# MorphingVCA.net
KiCad netlist of a schematic drawn in EAGLE
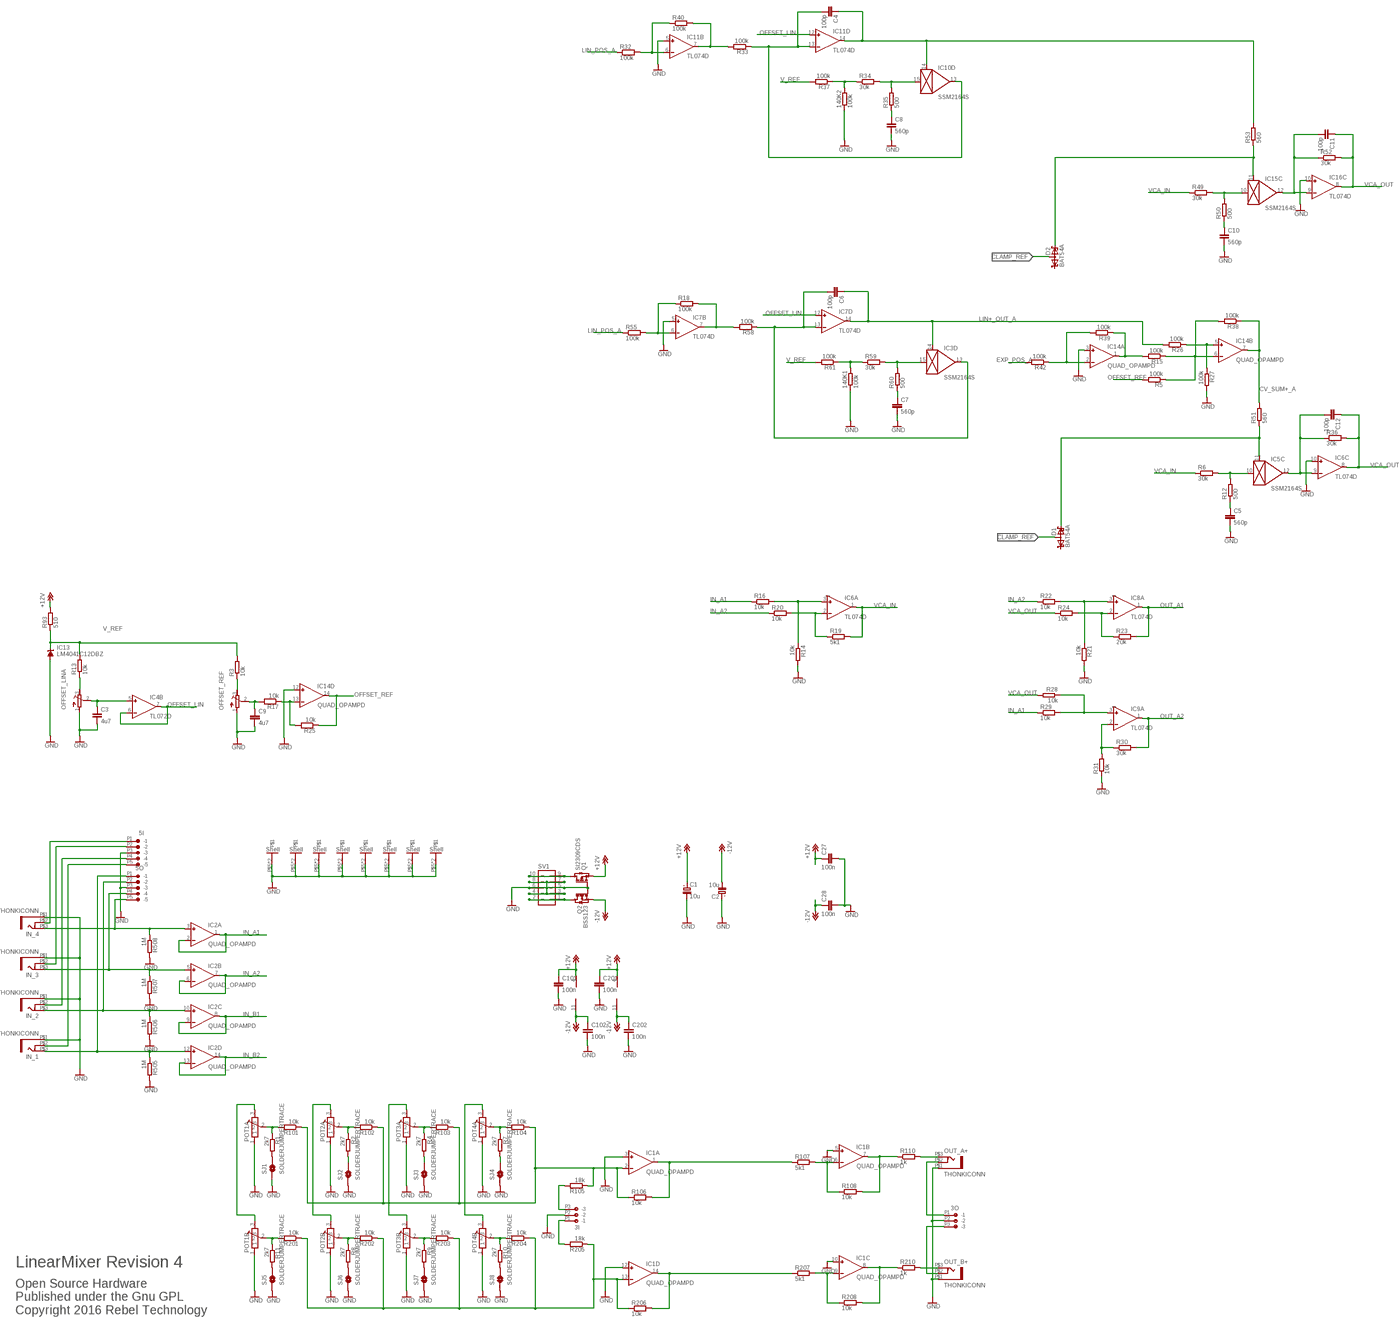
[diagram p0: schematic, sheet 1, overview]
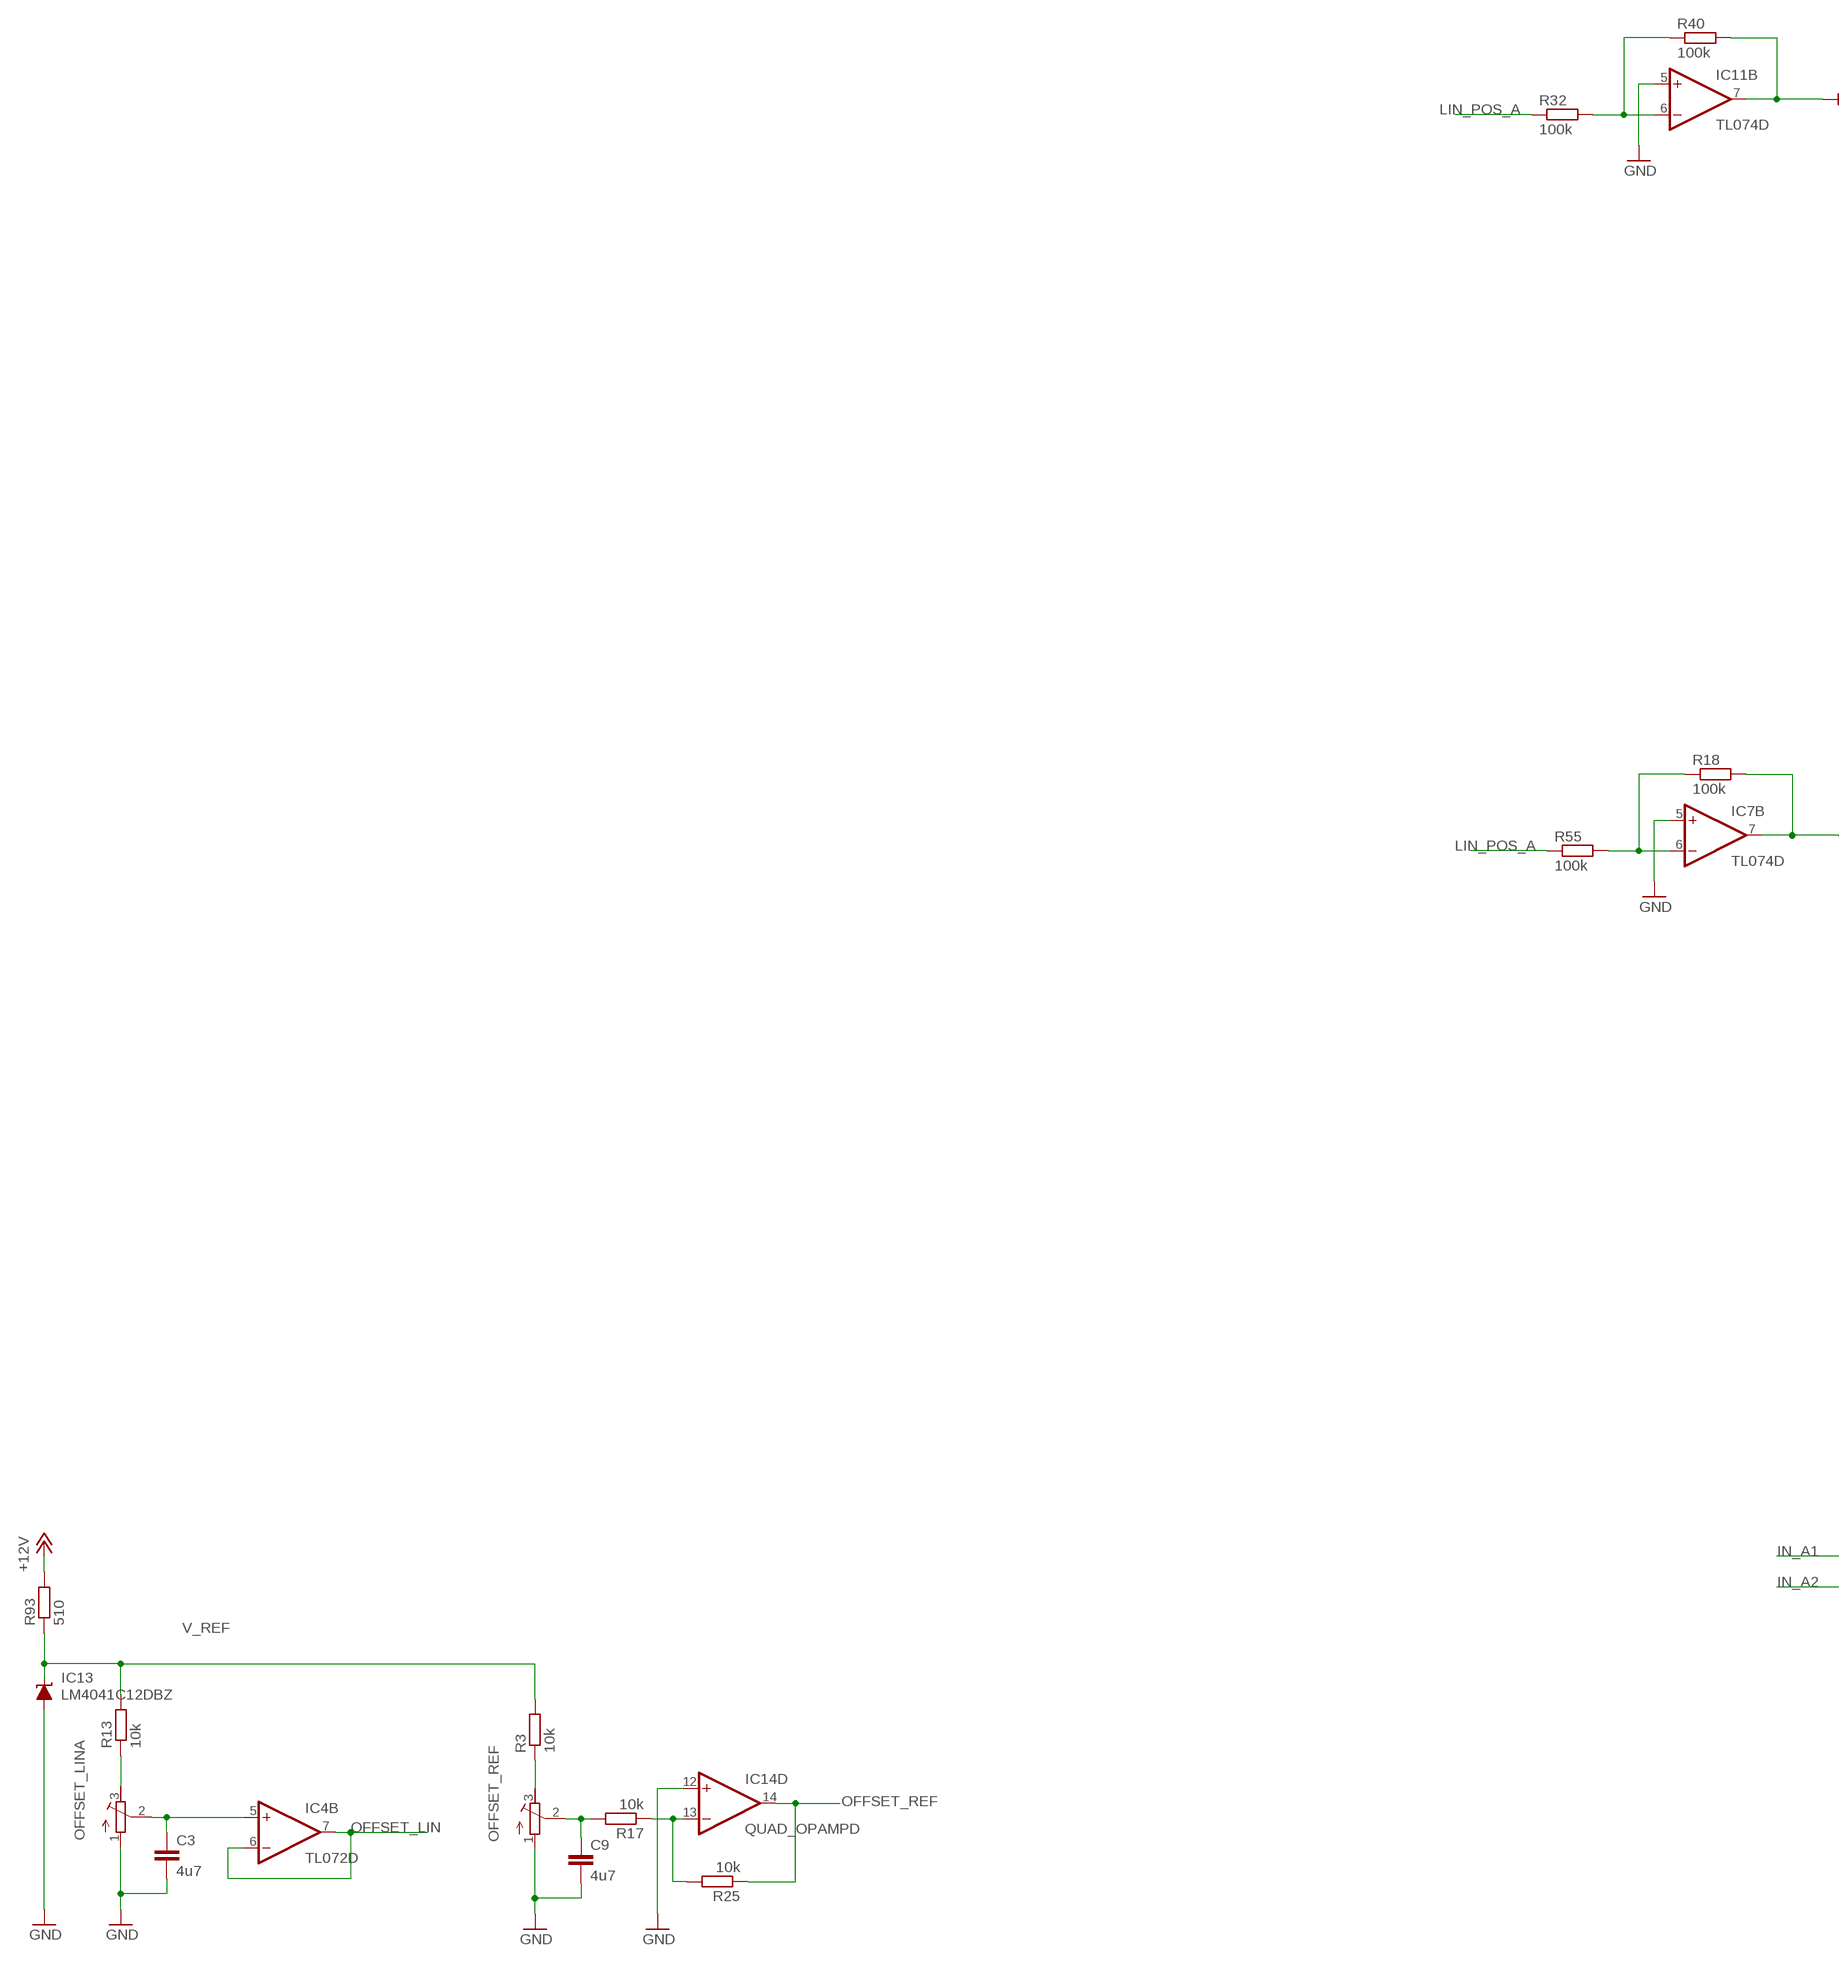
[diagram p1: schematic, sheet 1, part 1 of 4]
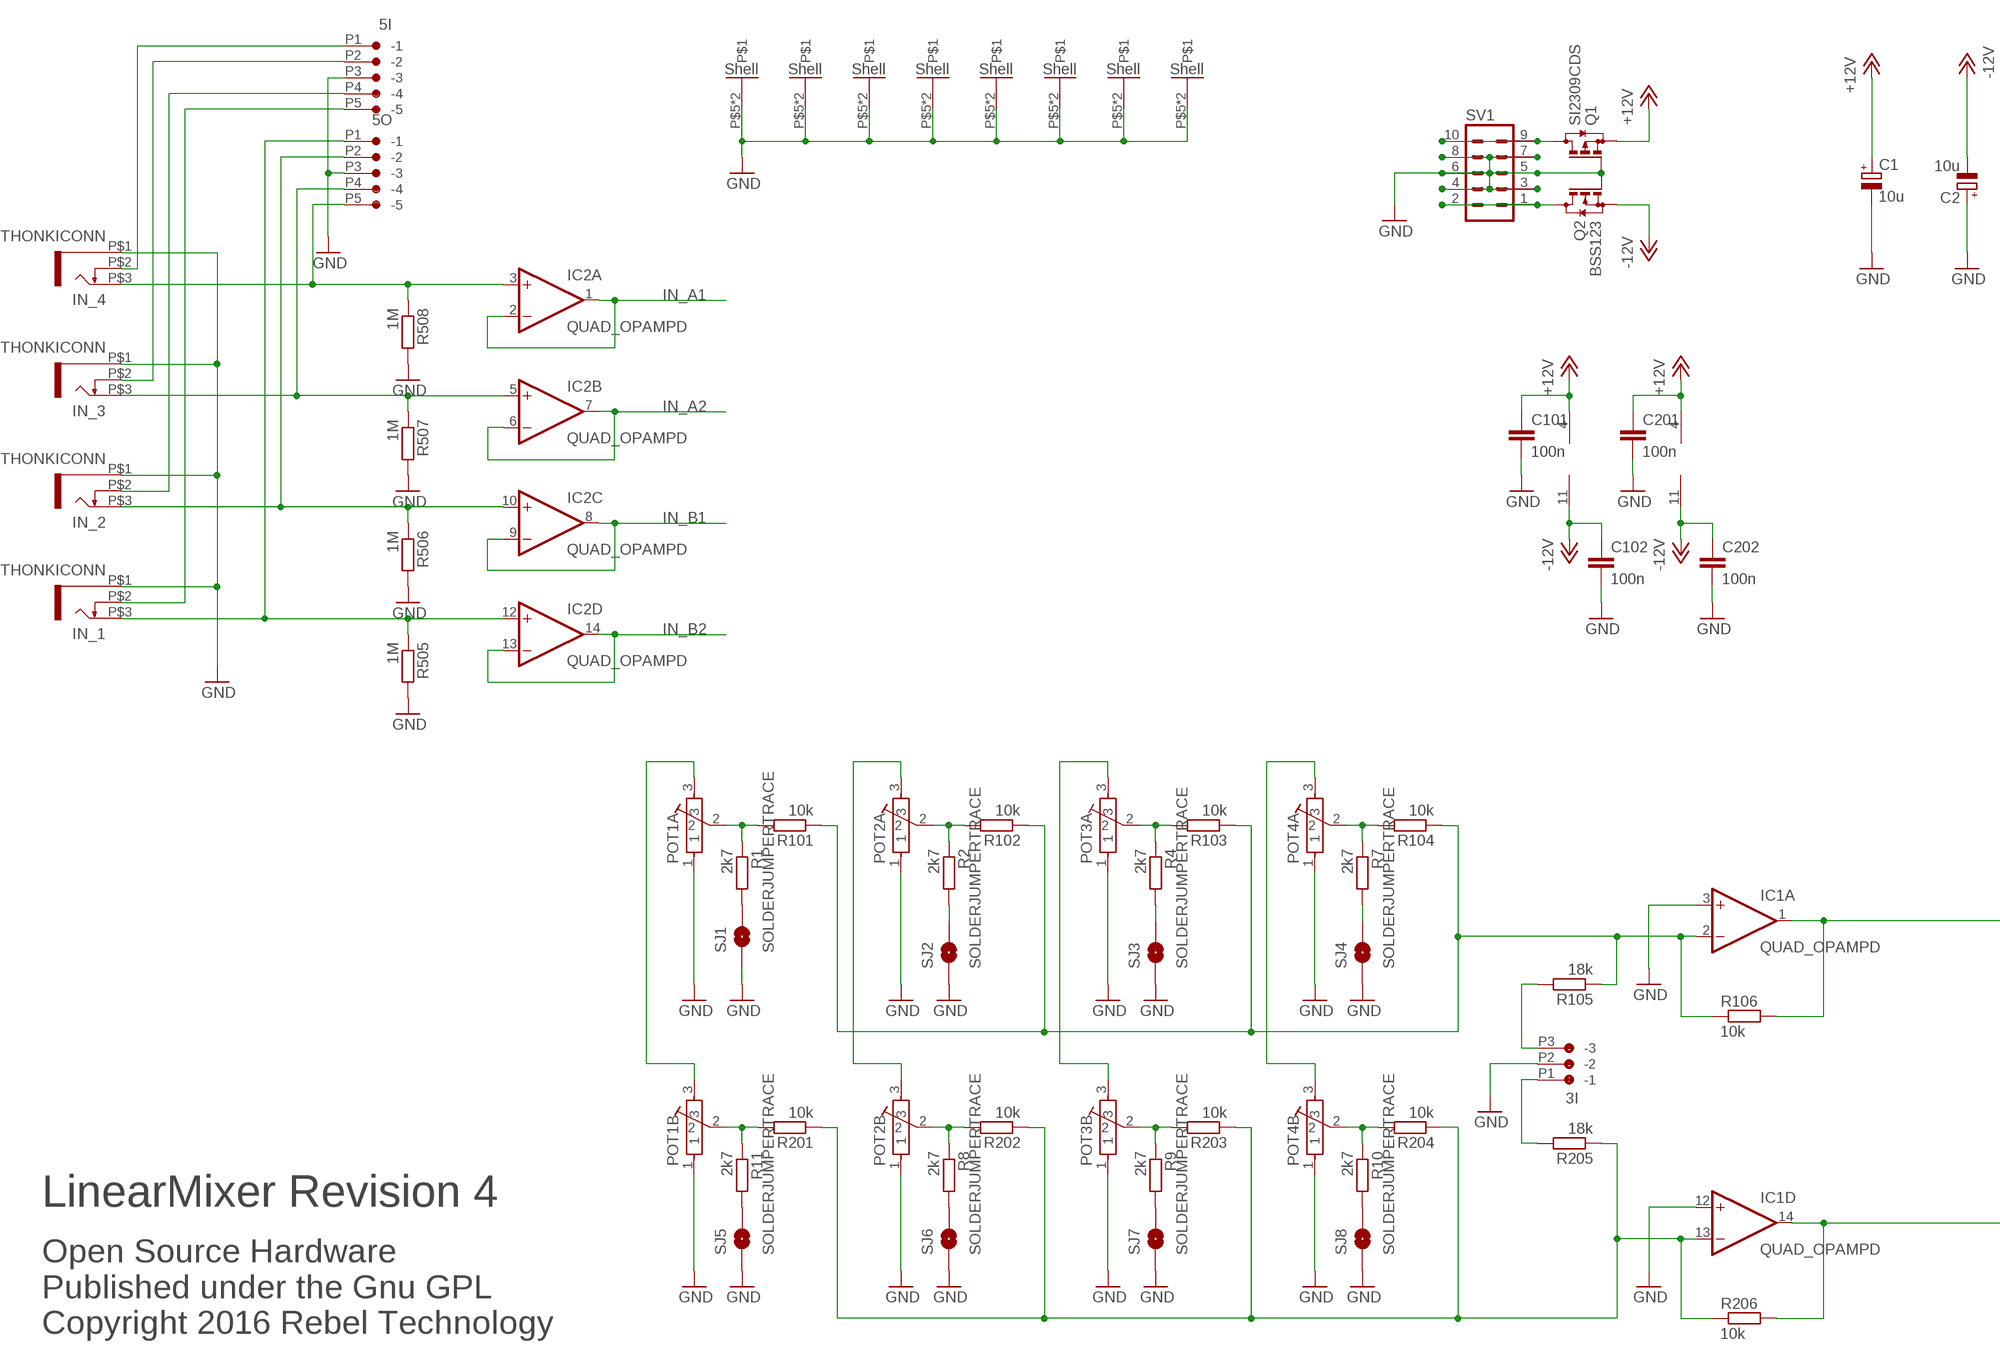
[diagram p2: schematic, sheet 1, part 2 of 4]
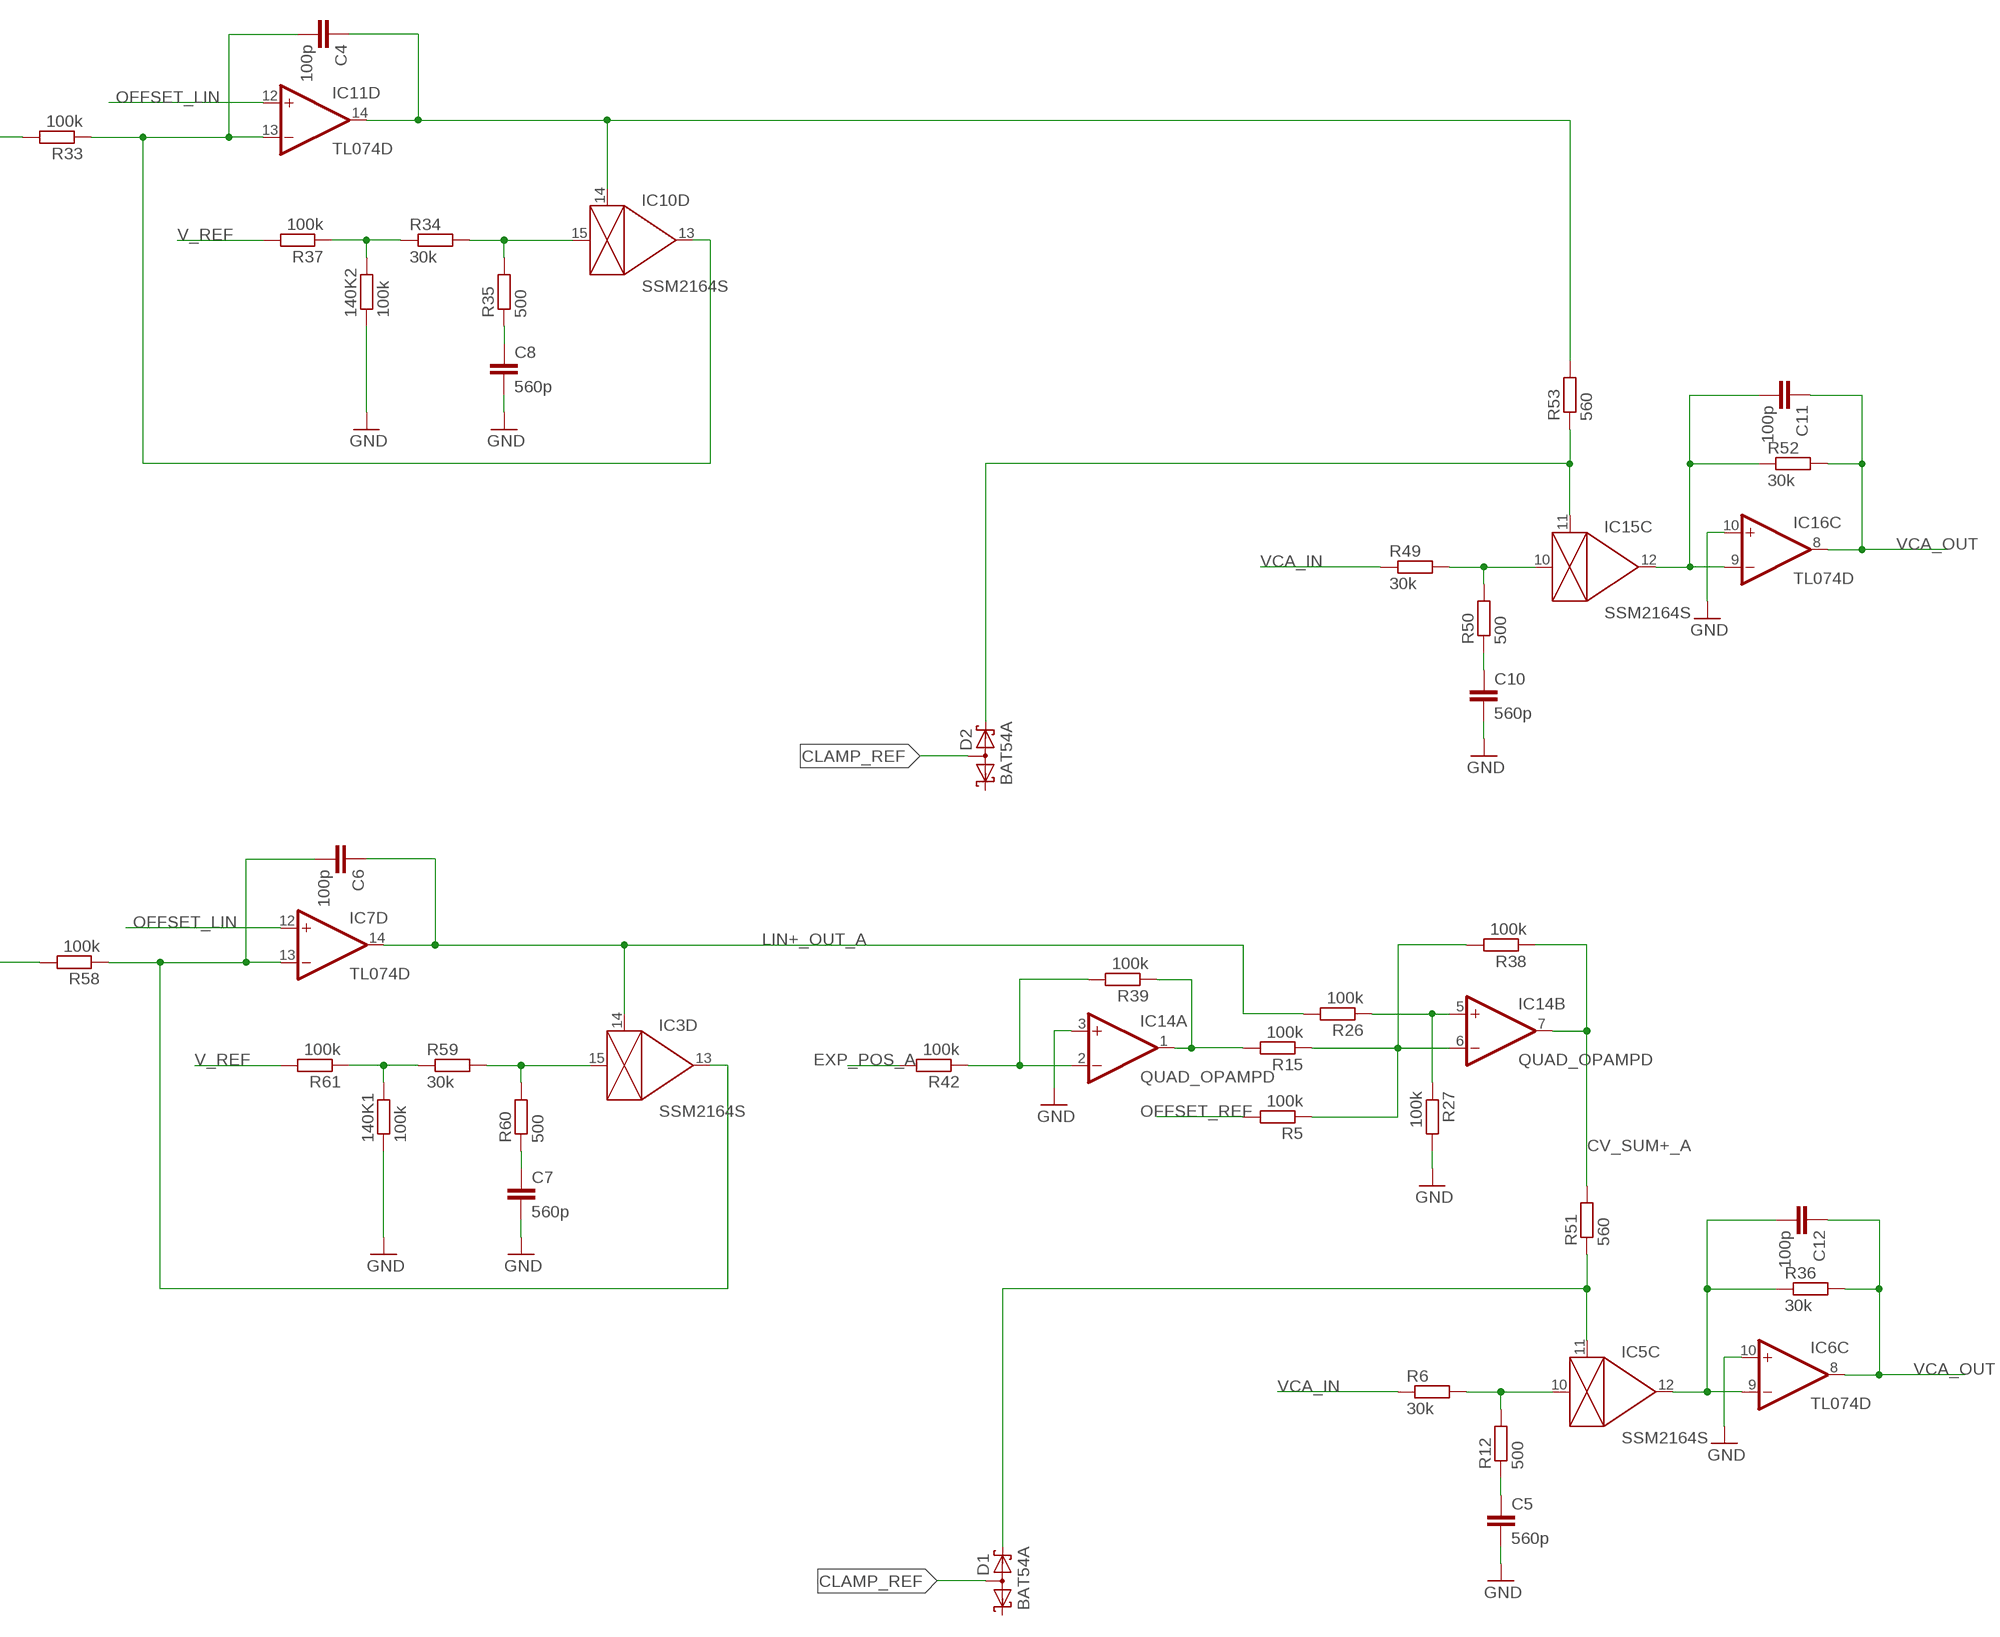
[diagram p3: schematic, sheet 1, part 3 of 4]
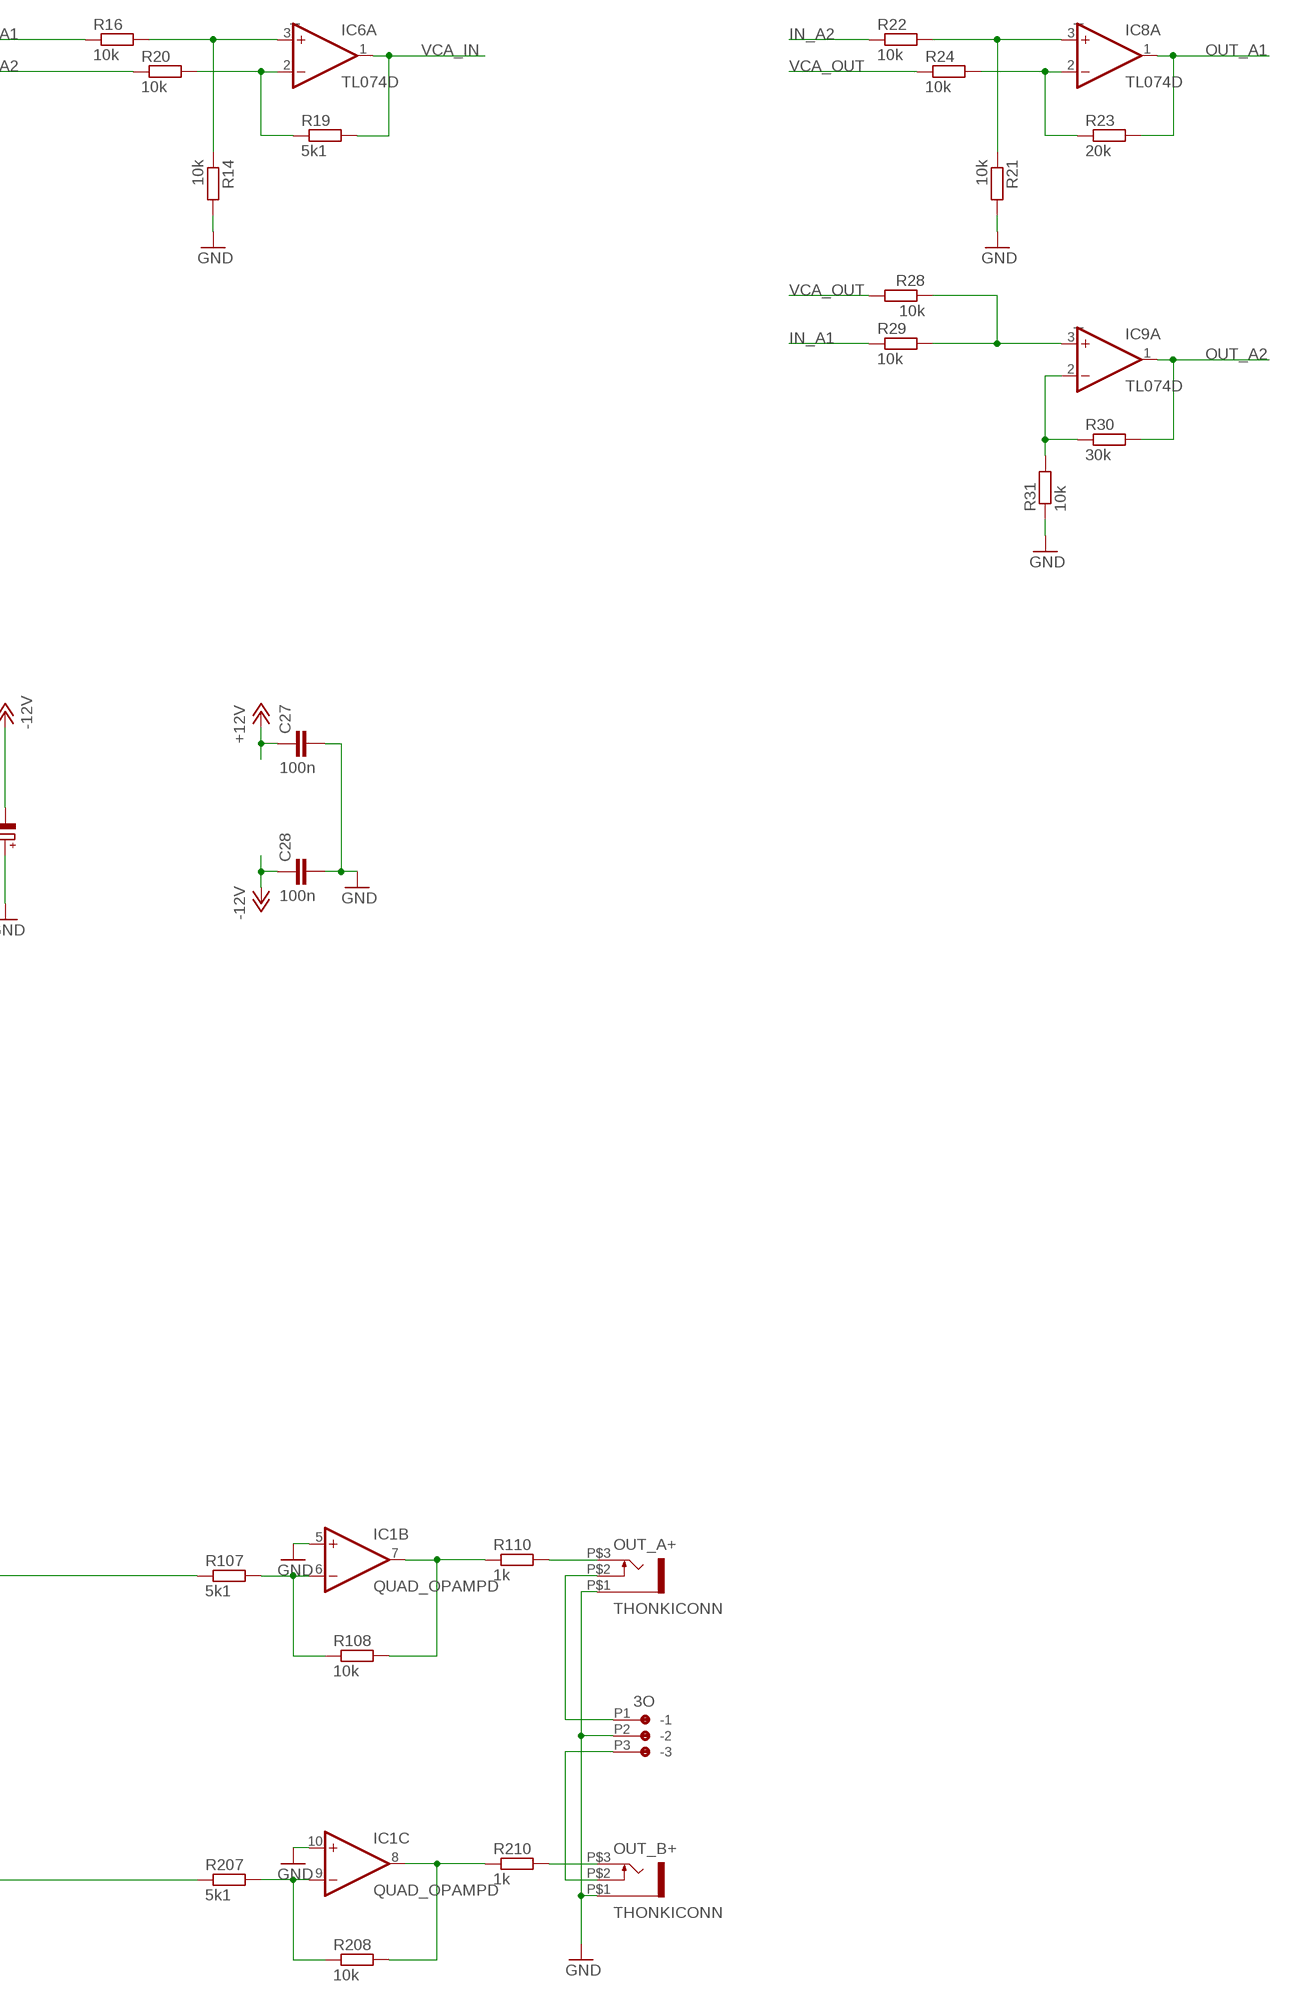
[diagram p4: schematic, sheet 1, part 4 of 4]

(export (version "E")
  (design (tool "Eeschema 10.0.6"))
  (components
    (comp (ref "3I")
      (value "CON-JST_PH_3W")
      (footprint "eagle-import:CON-JST_PH_3W")
      (libsource (lib "eagle-import") (part "CON-JST_PH_3W"))
    )
    (comp (ref "3O")
      (value "CON-JST_PH_3W")
      (footprint "eagle-import:CON-JST_PH_3W")
      (libsource (lib "eagle-import") (part "CON-JST_PH_3W"))
    )
    (comp (ref "5I")
      (value "CON-JST_PH_5W")
      (footprint "eagle-import:CON-JST_PH_5W")
      (libsource (lib "eagle-import") (part "CON-JST_PH_5W"))
    )
    (comp (ref "5O")
      (value "CON-JST_PH_5W")
      (footprint "eagle-import:CON-JST_PH_5W")
      (libsource (lib "eagle-import") (part "CON-JST_PH_5W"))
    )
    (comp (ref "140K1")
      (value "100k")
      (footprint "eagle-import:0603")
      (libsource (lib "eagle-import") (part "R-EU_0603"))
    )
    (comp (ref "140K2")
      (value "100k")
      (footprint "eagle-import:0603")
      (libsource (lib "eagle-import") (part "R-EU_0603"))
    )
    (comp (ref "C1")
      (value "10u")
      (footprint "eagle-import:153CLV-0505")
      (libsource (lib "eagle-import") (part "CPOL-EU153CLV-0505"))
    )
    (comp (ref "C2")
      (value "10u")
      (footprint "eagle-import:153CLV-0505")
      (libsource (lib "eagle-import") (part "CPOL-EU153CLV-0505"))
    )
    (comp (ref "C3")
      (value "4u7")
      (footprint "eagle-import:C0603K")
      (libsource (lib "eagle-import") (part "resistor_C-EUC0603K"))
    )
    (comp (ref "C4")
      (value "100p")
      (footprint "eagle-import:C0603K")
      (libsource (lib "eagle-import") (part "resistor_C-EUC0603K"))
    )
    (comp (ref "C5")
      (value "560p")
      (footprint "eagle-import:C0603K")
      (libsource (lib "eagle-import") (part "resistor_C-EUC0603K"))
    )
    (comp (ref "C6")
      (value "100p")
      (footprint "eagle-import:C0603K")
      (libsource (lib "eagle-import") (part "resistor_C-EUC0603K"))
    )
    (comp (ref "C7")
      (value "560p")
      (footprint "eagle-import:C0603K")
      (libsource (lib "eagle-import") (part "resistor_C-EUC0603K"))
    )
    (comp (ref "C8")
      (value "560p")
      (footprint "eagle-import:C0603K")
      (libsource (lib "eagle-import") (part "resistor_C-EUC0603K"))
    )
    (comp (ref "C9")
      (value "4u7")
      (footprint "eagle-import:C0603K")
      (libsource (lib "eagle-import") (part "resistor_C-EUC0603K"))
    )
    (comp (ref "C10")
      (value "560p")
      (footprint "eagle-import:C0603K")
      (libsource (lib "eagle-import") (part "resistor_C-EUC0603K"))
    )
    (comp (ref "C11")
      (value "100p")
      (footprint "eagle-import:C0603K")
      (libsource (lib "eagle-import") (part "resistor_C-EUC0603K"))
    )
    (comp (ref "C12")
      (value "100p")
      (footprint "eagle-import:C0603K")
      (libsource (lib "eagle-import") (part "resistor_C-EUC0603K"))
    )
    (comp (ref "C27")
      (value "100n")
      (footprint "eagle-import:C0603")
      (libsource (lib "eagle-import") (part "C-EUC0603"))
    )
    (comp (ref "C28")
      (value "100n")
      (footprint "eagle-import:C0603")
      (libsource (lib "eagle-import") (part "C-EUC0603"))
    )
    (comp (ref "C101")
      (value "100n")
      (footprint "eagle-import:C0603")
      (libsource (lib "eagle-import") (part "resistor_C-EUC0603"))
    )
    (comp (ref "C102")
      (value "100n")
      (footprint "eagle-import:C0603")
      (libsource (lib "eagle-import") (part "resistor_C-EUC0603"))
    )
    (comp (ref "C201")
      (value "100n")
      (footprint "eagle-import:C0603")
      (libsource (lib "eagle-import") (part "resistor_C-EUC0603"))
    )
    (comp (ref "C202")
      (value "100n")
      (footprint "eagle-import:C0603")
      (libsource (lib "eagle-import") (part "resistor_C-EUC0603"))
    )
    (comp (ref "D1")
      (value "BAT54A")
      (footprint "eagle-import:SOT23")
      (libsource (lib "eagle-import") (part "BAT54A"))
    )
    (comp (ref "D2")
      (value "BAT54A")
      (footprint "eagle-import:SOT23")
      (libsource (lib "eagle-import") (part "BAT54A"))
    )
    (comp (ref "IC1")
      (value "QUAD_OPAMPD")
      (footprint "eagle-import:SO14")
      (libsource (lib "eagle-import") (part "QUAD_OPAMPD"))
    )
    (comp (ref "IC2")
      (value "QUAD_OPAMPD")
      (footprint "eagle-import:SO14")
      (libsource (lib "eagle-import") (part "QUAD_OPAMPD"))
    )
    (comp (ref "IC3")
      (value "SSM2164S")
      (footprint "eagle-import:SOIC16N")
      (libsource (lib "eagle-import") (part "SSM2164S"))
    )
    (comp (ref "IC4")
      (value "TL072D")
      (footprint "eagle-import:SO08")
      (libsource (lib "eagle-import") (part "TL072D"))
    )
    (comp (ref "IC5")
      (value "SSM2164S")
      (footprint "eagle-import:SOIC16N")
      (fields (field (name "OC_FARNELL") "unknown"))
      (libsource (lib "eagle-import") (part "SSM2164S"))
    )
    (comp (ref "IC6")
      (value "TL074D")
      (footprint "eagle-import:SO14")
      (fields (field (name "OC_FARNELL") "unknown"))
      (libsource (lib "eagle-import") (part "TL074D"))
    )
    (comp (ref "IC7")
      (value "TL074D")
      (footprint "eagle-import:SO14")
      (fields (field (name "OC_FARNELL") "unknown"))
      (libsource (lib "eagle-import") (part "TL074D"))
    )
    (comp (ref "IC8")
      (value "TL074D")
      (footprint "eagle-import:SO14")
      (fields (field (name "OC_FARNELL") "unknown"))
      (libsource (lib "eagle-import") (part "TL074D"))
    )
    (comp (ref "IC9")
      (value "TL074D")
      (footprint "eagle-import:SO14")
      (fields (field (name "OC_FARNELL") "unknown"))
      (libsource (lib "eagle-import") (part "TL074D"))
    )
    (comp (ref "IC10")
      (value "SSM2164S")
      (footprint "eagle-import:SOIC16N")
      (libsource (lib "eagle-import") (part "SSM2164S"))
    )
    (comp (ref "IC11")
      (value "TL074D")
      (footprint "eagle-import:SO14")
      (fields (field (name "OC_FARNELL") "unknown"))
      (libsource (lib "eagle-import") (part "TL074D"))
    )
    (comp (ref "IC13")
      (value "LM4041C12DBZ")
      (footprint "eagle-import:DBZ_R-PDSO-G3")
      (fields (field (name "MF") "TEXAS INSTRUMENT CONNECTORS") (field (name "MPN") "LM4041C12QDBZT"))
      (libsource (lib "eagle-import") (part "LM4041DBZC12"))
    )
    (comp (ref "IC14")
      (value "QUAD_OPAMPD")
      (footprint "eagle-import:SO14")
      (libsource (lib "eagle-import") (part "QUAD_OPAMPD"))
    )
    (comp (ref "IC15")
      (value "SSM2164S")
      (footprint "eagle-import:SOIC16N")
      (fields (field (name "OC_FARNELL") "unknown"))
      (libsource (lib "eagle-import") (part "SSM2164S"))
    )
    (comp (ref "IC16")
      (value "TL074D")
      (footprint "eagle-import:SO14")
      (libsource (lib "eagle-import") (part "TL074D"))
    )
    (comp (ref "IN_1")
      (value "THONKICONN")
      (footprint "eagle-import:THONKICONN")
      (libsource (lib "eagle-import") (part "THONKICONN"))
    )
    (comp (ref "IN_2")
      (value "THONKICONN")
      (footprint "eagle-import:THONKICONN")
      (libsource (lib "eagle-import") (part "THONKICONN"))
    )
    (comp (ref "IN_3")
      (value "THONKICONN")
      (footprint "eagle-import:THONKICONN")
      (libsource (lib "eagle-import") (part "THONKICONN"))
    )
    (comp (ref "IN_4")
      (value "THONKICONN")
      (footprint "eagle-import:THONKICONN")
      (libsource (lib "eagle-import") (part "THONKICONN"))
    )
    (comp (ref "OFFSET_LINA")
      (value "R-TRIMM64W")
      (footprint "eagle-import:RTRIM64W")
      (libsource (lib "eagle-import") (part "R-TRIMM64W"))
    )
    (comp (ref "OFFSET_REF")
      (value "R-TRIMM64W")
      (footprint "eagle-import:RTRIM64W")
      (libsource (lib "eagle-import") (part "R-TRIMM64W"))
    )
    (comp (ref "OUT_A+")
      (value "THONKICONN")
      (footprint "eagle-import:THONKICONN")
      (libsource (lib "eagle-import") (part "THONKICONN"))
    )
    (comp (ref "OUT_B+")
      (value "THONKICONN")
      (footprint "eagle-import:THONKICONN")
      (libsource (lib "eagle-import") (part "THONKICONN"))
    )
    (comp (ref "POT1A")
      (value "POT-ALPS-RK09L1140")
      (footprint "eagle-import:POT-ALPS-RK09L1140")
      (libsource (lib "eagle-import") (part "POT-ALPS-RK09L1140"))
    )
    (comp (ref "POT1B")
      (value "POT-ALPS-RK09L1140")
      (footprint "eagle-import:POT-ALPS-RK09L1140")
      (libsource (lib "eagle-import") (part "POT-ALPS-RK09L1140"))
    )
    (comp (ref "POT2A")
      (value "POT-ALPS-RK09L1140")
      (footprint "eagle-import:POT-ALPS-RK09L1140")
      (libsource (lib "eagle-import") (part "POT-ALPS-RK09L1140"))
    )
    (comp (ref "POT2B")
      (value "POT-ALPS-RK09L1140")
      (footprint "eagle-import:POT-ALPS-RK09L1140")
      (libsource (lib "eagle-import") (part "POT-ALPS-RK09L1140"))
    )
    (comp (ref "POT3A")
      (value "POT-ALPS-RK09L1140")
      (footprint "eagle-import:POT-ALPS-RK09L1140")
      (libsource (lib "eagle-import") (part "POT-ALPS-RK09L1140"))
    )
    (comp (ref "POT3B")
      (value "POT-ALPS-RK09L1140")
      (footprint "eagle-import:POT-ALPS-RK09L1140")
      (libsource (lib "eagle-import") (part "POT-ALPS-RK09L1140"))
    )
    (comp (ref "POT4A")
      (value "POT-ALPS-RK09L1140")
      (footprint "eagle-import:POT-ALPS-RK09L1140")
      (libsource (lib "eagle-import") (part "POT-ALPS-RK09L1140"))
    )
    (comp (ref "POT4B")
      (value "POT-ALPS-RK09L1140")
      (footprint "eagle-import:POT-ALPS-RK09L1140")
      (libsource (lib "eagle-import") (part "POT-ALPS-RK09L1140"))
    )
    (comp (ref "Q1")
      (value "SI2309CDS")
      (footprint "eagle-import:SOT23")
      (libsource (lib "eagle-import") (part "BSS84"))
    )
    (comp (ref "Q2")
      (value "BSS123")
      (footprint "eagle-import:SOT23")
      (libsource (lib "eagle-import") (part "BSS123"))
    )
    (comp (ref "R1")
      (value "2k7")
      (footprint "eagle-import:R0603")
      (libsource (lib "eagle-import") (part "R-EU_R0603"))
    )
    (comp (ref "R2")
      (value "2k7")
      (footprint "eagle-import:R0603")
      (libsource (lib "eagle-import") (part "R-EU_R0603"))
    )
    (comp (ref "R3")
      (value "10k")
      (footprint "eagle-import:0603")
      (libsource (lib "eagle-import") (part "R-EU_0603"))
    )
    (comp (ref "R4")
      (value "2k7")
      (footprint "eagle-import:R0603")
      (libsource (lib "eagle-import") (part "R-EU_R0603"))
    )
    (comp (ref "R5")
      (value "100k")
      (footprint "eagle-import:0603")
      (libsource (lib "eagle-import") (part "R-EU_0603"))
    )
    (comp (ref "R6")
      (value "30k")
      (footprint "eagle-import:0603")
      (libsource (lib "eagle-import") (part "R-EU_0603"))
    )
    (comp (ref "R7")
      (value "2k7")
      (footprint "eagle-import:R0603")
      (libsource (lib "eagle-import") (part "R-EU_R0603"))
    )
    (comp (ref "R8")
      (value "2k7")
      (footprint "eagle-import:R0603")
      (libsource (lib "eagle-import") (part "R-EU_R0603"))
    )
    (comp (ref "R9")
      (value "2k7")
      (footprint "eagle-import:R0603")
      (libsource (lib "eagle-import") (part "R-EU_R0603"))
    )
    (comp (ref "R10")
      (value "2k7")
      (footprint "eagle-import:R0603")
      (libsource (lib "eagle-import") (part "R-EU_R0603"))
    )
    (comp (ref "R11")
      (value "2k7")
      (footprint "eagle-import:R0603")
      (libsource (lib "eagle-import") (part "R-EU_R0603"))
    )
    (comp (ref "R12")
      (value "500")
      (footprint "eagle-import:0603")
      (libsource (lib "eagle-import") (part "R-EU_0603"))
    )
    (comp (ref "R13")
      (value "10k")
      (footprint "eagle-import:0603")
      (libsource (lib "eagle-import") (part "R-EU_0603"))
    )
    (comp (ref "R14")
      (value "10k")
      (footprint "eagle-import:0603")
      (libsource (lib "eagle-import") (part "R-EU_0603"))
    )
    (comp (ref "R15")
      (value "100k")
      (footprint "eagle-import:0603")
      (libsource (lib "eagle-import") (part "R-EU_0603"))
    )
    (comp (ref "R16")
      (value "10k")
      (footprint "eagle-import:0603")
      (libsource (lib "eagle-import") (part "R-EU_0603"))
    )
    (comp (ref "R17")
      (value "10k")
      (footprint "eagle-import:0603")
      (libsource (lib "eagle-import") (part "R-EU_0603"))
    )
    (comp (ref "R18")
      (value "100k")
      (footprint "eagle-import:0603")
      (libsource (lib "eagle-import") (part "R-EU_0603"))
    )
    (comp (ref "R19")
      (value "5k1")
      (footprint "eagle-import:0603")
      (libsource (lib "eagle-import") (part "R-EU_0603"))
    )
    (comp (ref "R20")
      (value "10k")
      (footprint "eagle-import:0603")
      (libsource (lib "eagle-import") (part "R-EU_0603"))
    )
    (comp (ref "R21")
      (value "10k")
      (footprint "eagle-import:0603")
      (libsource (lib "eagle-import") (part "R-EU_0603"))
    )
    (comp (ref "R22")
      (value "10k")
      (footprint "eagle-import:0603")
      (libsource (lib "eagle-import") (part "R-EU_0603"))
    )
    (comp (ref "R23")
      (value "20k")
      (footprint "eagle-import:0603")
      (libsource (lib "eagle-import") (part "R-EU_0603"))
    )
    (comp (ref "R24")
      (value "10k")
      (footprint "eagle-import:0603")
      (libsource (lib "eagle-import") (part "R-EU_0603"))
    )
    (comp (ref "R25")
      (value "10k")
      (footprint "eagle-import:0603")
      (libsource (lib "eagle-import") (part "R-EU_0603"))
    )
    (comp (ref "R26")
      (value "100k")
      (footprint "eagle-import:0603")
      (libsource (lib "eagle-import") (part "R-EU_0603"))
    )
    (comp (ref "R27")
      (value "100k")
      (footprint "eagle-import:0603")
      (libsource (lib "eagle-import") (part "R-EU_0603"))
    )
    (comp (ref "R28")
      (value "10k")
      (footprint "eagle-import:0603")
      (libsource (lib "eagle-import") (part "R-EU_0603"))
    )
    (comp (ref "R29")
      (value "10k")
      (footprint "eagle-import:0603")
      (libsource (lib "eagle-import") (part "R-EU_0603"))
    )
    (comp (ref "R30")
      (value "30k")
      (footprint "eagle-import:0603")
      (libsource (lib "eagle-import") (part "R-EU_0603"))
    )
    (comp (ref "R31")
      (value "10k")
      (footprint "eagle-import:0603")
      (libsource (lib "eagle-import") (part "R-EU_0603"))
    )
    (comp (ref "R32")
      (value "100k")
      (footprint "eagle-import:0603")
      (libsource (lib "eagle-import") (part "R-EU_0603"))
    )
    (comp (ref "R33")
      (value "100k")
      (footprint "eagle-import:0603")
      (libsource (lib "eagle-import") (part "R-EU_0603"))
    )
    (comp (ref "R34")
      (value "30k")
      (footprint "eagle-import:0603")
      (libsource (lib "eagle-import") (part "R-EU_0603"))
    )
    (comp (ref "R35")
      (value "500")
      (footprint "eagle-import:0603")
      (libsource (lib "eagle-import") (part "R-EU_0603"))
    )
    (comp (ref "R36")
      (value "30k")
      (footprint "eagle-import:0603")
      (libsource (lib "eagle-import") (part "R-EU_0603"))
    )
    (comp (ref "R37")
      (value "100k")
      (footprint "eagle-import:0603")
      (libsource (lib "eagle-import") (part "R-EU_0603"))
    )
    (comp (ref "R38")
      (value "100k")
      (footprint "eagle-import:0603")
      (libsource (lib "eagle-import") (part "R-EU_0603"))
    )
    (comp (ref "R39")
      (value "100k")
      (footprint "eagle-import:0603")
      (libsource (lib "eagle-import") (part "R-EU_0603"))
    )
    (comp (ref "R40")
      (value "100k")
      (footprint "eagle-import:0603")
      (libsource (lib "eagle-import") (part "R-EU_0603"))
    )
    (comp (ref "R42")
      (value "100k")
      (footprint "eagle-import:0603")
      (libsource (lib "eagle-import") (part "R-EU_0603"))
    )
    (comp (ref "R49")
      (value "30k")
      (footprint "eagle-import:0603")
      (libsource (lib "eagle-import") (part "R-EU_0603"))
    )
    (comp (ref "R50")
      (value "500")
      (footprint "eagle-import:0603")
      (libsource (lib "eagle-import") (part "R-EU_0603"))
    )
    (comp (ref "R51")
      (value "560")
      (footprint "eagle-import:0603")
      (libsource (lib "eagle-import") (part "R-EU_0603"))
    )
    (comp (ref "R52")
      (value "30k")
      (footprint "eagle-import:0603")
      (libsource (lib "eagle-import") (part "R-EU_0603"))
    )
    (comp (ref "R53")
      (value "560")
      (footprint "eagle-import:0603")
      (libsource (lib "eagle-import") (part "R-EU_0603"))
    )
    (comp (ref "R55")
      (value "100k")
      (footprint "eagle-import:0603")
      (libsource (lib "eagle-import") (part "R-EU_0603"))
    )
    (comp (ref "R58")
      (value "100k")
      (footprint "eagle-import:0603")
      (libsource (lib "eagle-import") (part "R-EU_0603"))
    )
    (comp (ref "R59")
      (value "30k")
      (footprint "eagle-import:0603")
      (libsource (lib "eagle-import") (part "R-EU_0603"))
    )
    (comp (ref "R60")
      (value "500")
      (footprint "eagle-import:0603")
      (libsource (lib "eagle-import") (part "R-EU_0603"))
    )
    (comp (ref "R61")
      (value "100k")
      (footprint "eagle-import:0603")
      (libsource (lib "eagle-import") (part "R-EU_0603"))
    )
    (comp (ref "R93")
      (value "510")
      (footprint "eagle-import:0603")
      (libsource (lib "eagle-import") (part "R-EU_0603"))
    )
    (comp (ref "R101")
      (value "10k")
      (footprint "eagle-import:R0603")
      (libsource (lib "eagle-import") (part "R-EU_R0603"))
    )
    (comp (ref "R102")
      (value "10k")
      (footprint "eagle-import:R0603")
      (libsource (lib "eagle-import") (part "R-EU_R0603"))
    )
    (comp (ref "R103")
      (value "10k")
      (footprint "eagle-import:R0603")
      (libsource (lib "eagle-import") (part "R-EU_R0603"))
    )
    (comp (ref "R104")
      (value "10k")
      (footprint "eagle-import:R0603")
      (libsource (lib "eagle-import") (part "R-EU_R0603"))
    )
    (comp (ref "R105")
      (value "18k")
      (footprint "eagle-import:R0603")
      (libsource (lib "eagle-import") (part "R-EU_R0603"))
    )
    (comp (ref "R106")
      (value "10k")
      (footprint "eagle-import:R0603")
      (libsource (lib "eagle-import") (part "R-EU_R0603"))
    )
    (comp (ref "R107")
      (value "5k1")
      (footprint "eagle-import:R0603")
      (libsource (lib "eagle-import") (part "R-EU_R0603"))
    )
    (comp (ref "R108")
      (value "10k")
      (footprint "eagle-import:R0603")
      (libsource (lib "eagle-import") (part "R-EU_R0603"))
    )
    (comp (ref "R110")
      (value "1k")
      (footprint "eagle-import:R0603")
      (libsource (lib "eagle-import") (part "R-EU_R0603"))
    )
    (comp (ref "R201")
      (value "10k")
      (footprint "eagle-import:R0603")
      (libsource (lib "eagle-import") (part "R-EU_R0603"))
    )
    (comp (ref "R202")
      (value "10k")
      (footprint "eagle-import:R0603")
      (libsource (lib "eagle-import") (part "R-EU_R0603"))
    )
    (comp (ref "R203")
      (value "10k")
      (footprint "eagle-import:R0603")
      (libsource (lib "eagle-import") (part "R-EU_R0603"))
    )
    (comp (ref "R204")
      (value "10k")
      (footprint "eagle-import:R0603")
      (libsource (lib "eagle-import") (part "R-EU_R0603"))
    )
    (comp (ref "R205")
      (value "18k")
      (footprint "eagle-import:R0603")
      (libsource (lib "eagle-import") (part "R-EU_R0603"))
    )
    (comp (ref "R206")
      (value "10k")
      (footprint "eagle-import:R0603")
      (libsource (lib "eagle-import") (part "R-EU_R0603"))
    )
    (comp (ref "R207")
      (value "5k1")
      (footprint "eagle-import:R0603")
      (libsource (lib "eagle-import") (part "R-EU_R0603"))
    )
    (comp (ref "R208")
      (value "10k")
      (footprint "eagle-import:R0603")
      (libsource (lib "eagle-import") (part "R-EU_R0603"))
    )
    (comp (ref "R210")
      (value "1k")
      (footprint "eagle-import:R0603")
      (libsource (lib "eagle-import") (part "R-EU_R0603"))
    )
    (comp (ref "R505")
      (value "1M")
      (footprint "eagle-import:R0603")
      (libsource (lib "eagle-import") (part "R-EU_R0603"))
    )
    (comp (ref "R506")
      (value "1M")
      (footprint "eagle-import:R0603")
      (libsource (lib "eagle-import") (part "R-EU_R0603"))
    )
    (comp (ref "R507")
      (value "1M")
      (footprint "eagle-import:R0603")
      (libsource (lib "eagle-import") (part "R-EU_R0603"))
    )
    (comp (ref "R508")
      (value "1M")
      (footprint "eagle-import:R0603")
      (libsource (lib "eagle-import") (part "R-EU_R0603"))
    )
    (comp (ref "SJ1")
      (value "SOLDERJUMPERTRACE")
      (footprint "eagle-import:SJ_2S-TRACE")
      (libsource (lib "eagle-import") (part "SOLDERJUMPERTRACE"))
    )
    (comp (ref "SJ2")
      (value "SOLDERJUMPERTRACE")
      (footprint "eagle-import:SJ_2S-TRACE")
      (libsource (lib "eagle-import") (part "SOLDERJUMPERTRACE"))
    )
    (comp (ref "SJ3")
      (value "SOLDERJUMPERTRACE")
      (footprint "eagle-import:SJ_2S-TRACE")
      (libsource (lib "eagle-import") (part "SOLDERJUMPERTRACE"))
    )
    (comp (ref "SJ4")
      (value "SOLDERJUMPERTRACE")
      (footprint "eagle-import:SJ_2S-TRACE")
      (libsource (lib "eagle-import") (part "SOLDERJUMPERTRACE"))
    )
    (comp (ref "SJ5")
      (value "SOLDERJUMPERTRACE")
      (footprint "eagle-import:SJ_2S-TRACE")
      (libsource (lib "eagle-import") (part "SOLDERJUMPERTRACE"))
    )
    (comp (ref "SJ6")
      (value "SOLDERJUMPERTRACE")
      (footprint "eagle-import:SJ_2S-TRACE")
      (libsource (lib "eagle-import") (part "SOLDERJUMPERTRACE"))
    )
    (comp (ref "SJ7")
      (value "SOLDERJUMPERTRACE")
      (footprint "eagle-import:SJ_2S-TRACE")
      (libsource (lib "eagle-import") (part "SOLDERJUMPERTRACE"))
    )
    (comp (ref "SJ8")
      (value "SOLDERJUMPERTRACE")
      (footprint "eagle-import:SJ_2S-TRACE")
      (libsource (lib "eagle-import") (part "SOLDERJUMPERTRACE"))
    )
    (comp (ref "SV1")
      (value "MA05-2")
      (footprint "eagle-import:MA05-2")
      (libsource (lib "eagle-import") (part "MA05-2"))
    )
  )
  (nets
    (net (code "1") (name "+12V") (class "Default")
      (node (ref "C1") (pin "+") (pinfunction "+_+") (pintype "passive"))
      (node (ref "C101") (pin "1") (pinfunction "1_1") (pintype "passive"))
      (node (ref "C201") (pin "1") (pinfunction "1_1") (pintype "passive"))
      (node (ref "C27") (pin "1") (pinfunction "1_1") (pintype "passive"))
      (node (ref "IC1") (pin "4") (pinfunction "V+_4") (pintype "power_in"))
      (node (ref "IC2") (pin "4") (pinfunction "V+_4") (pintype "power_in"))
      (node (ref "Q1") (pin "2") (pinfunction "S_2") (pintype "passive"))
      (node (ref "R93") (pin "2") (pinfunction "2_2") (pintype "passive"))
    )
    (net (code "2") (name "-12V") (class "Default")
      (node (ref "C102") (pin "1") (pinfunction "1_1") (pintype "passive"))
      (node (ref "C2") (pin "-") (pinfunction "-_-") (pintype "passive"))
      (node (ref "C202") (pin "1") (pinfunction "1_1") (pintype "passive"))
      (node (ref "C28") (pin "1") (pinfunction "1_1") (pintype "passive"))
      (node (ref "IC1") (pin "11") (pinfunction "V-_11") (pintype "power_in"))
      (node (ref "IC2") (pin "11") (pinfunction "V-_11") (pintype "power_in"))
      (node (ref "Q2") (pin "2") (pinfunction "S_2") (pintype "passive"))
    )
    (net (code "3") (name "/CV_SUM+_A") (class "Default")
      (node (ref "IC14") (pin "7") (pinfunction "OUT_7") (pintype "output"))
      (node (ref "R38") (pin "1") (pinfunction "1_1") (pintype "passive"))
      (node (ref "R51") (pin "2") (pinfunction "2_2") (pintype "passive"))
    )
    (net (code "4") (name "/EXP_POS_A") (class "Default")
      (node (ref "R42") (pin "2") (pinfunction "2_2") (pintype "passive"))
    )
    (net (code "5") (name "/IN_A1") (class "Default")
      (node (ref "IC2") (pin "1") (pinfunction "OUT_1") (pintype "output"))
      (node (ref "IC2") (pin "2") (pinfunction "-IN_2") (pintype "input"))
      (node (ref "R16") (pin "1") (pinfunction "1_1") (pintype "passive"))
    )
    (net (code "6") (name "/IN_A2") (class "Default")
      (node (ref "IC2") (pin "6") (pinfunction "-IN_6") (pintype "input"))
      (node (ref "IC2") (pin "7") (pinfunction "OUT_7") (pintype "output"))
      (node (ref "R20") (pin "1") (pinfunction "1_1") (pintype "passive"))
      (node (ref "R22") (pin "1") (pinfunction "1_1") (pintype "passive"))
    )
    (net (code "7") (name "/IN_B1") (class "Default")
      (node (ref "IC2") (pin "8") (pinfunction "OUT_8") (pintype "output"))
      (node (ref "IC2") (pin "9") (pinfunction "-IN_9") (pintype "input"))
    )
    (net (code "8") (name "/IN_B2") (class "Default")
      (node (ref "IC2") (pin "13") (pinfunction "-IN_13") (pintype "input"))
      (node (ref "IC2") (pin "14") (pinfunction "OUT_14") (pintype "output"))
    )
    (net (code "9") (name "/LIN+_OUT_A") (class "Default")
      (node (ref "C4") (pin "1") (pinfunction "1_1") (pintype "passive"))
      (node (ref "C6") (pin "1") (pinfunction "1_1") (pintype "passive"))
      (node (ref "IC10") (pin "14") (pinfunction "CTRL_14") (pintype "input"))
      (node (ref "IC11") (pin "14") (pinfunction "OUT_14") (pintype "output"))
      (node (ref "IC3") (pin "14") (pinfunction "CTRL_14") (pintype "input"))
      (node (ref "IC7") (pin "14") (pinfunction "OUT_14") (pintype "output"))
      (node (ref "R26") (pin "2") (pinfunction "2_2") (pintype "passive"))
      (node (ref "R53") (pin "2") (pinfunction "2_2") (pintype "passive"))
    )
    (net (code "10") (name "/LIN_POS_A") (class "Default")
      (node (ref "R32") (pin "1") (pinfunction "1_1") (pintype "passive"))
      (node (ref "R55") (pin "1") (pinfunction "1_1") (pintype "passive"))
    )
    (net (code "11") (name "/OFFSET_LIN") (class "Default")
      (node (ref "IC11") (pin "12") (pinfunction "+IN_12") (pintype "input"))
      (node (ref "IC4") (pin "6") (pinfunction "-IN_6") (pintype "input"))
      (node (ref "IC4") (pin "7") (pinfunction "OUT_7") (pintype "output"))
      (node (ref "IC7") (pin "12") (pinfunction "+IN_12") (pintype "input"))
    )
    (net (code "12") (name "/OFFSET_REF") (class "Default")
      (node (ref "IC14") (pin "14") (pinfunction "OUT_14") (pintype "output"))
      (node (ref "R25") (pin "1") (pinfunction "1_1") (pintype "passive"))
      (node (ref "R5") (pin "2") (pinfunction "2_2") (pintype "passive"))
    )
    (net (code "13") (name "/OUT_A1") (class "Default")
      (node (ref "IC8") (pin "1") (pinfunction "OUT_1") (pintype "output"))
      (node (ref "R23") (pin "2") (pinfunction "2_2") (pintype "passive"))
    )
    (net (code "14") (name "/OUT_A2") (class "Default")
      (node (ref "IC9") (pin "1") (pinfunction "OUT_1") (pintype "output"))
      (node (ref "R30") (pin "2") (pinfunction "2_2") (pintype "passive"))
    )
    (net (code "15") (name "/VCA_IN") (class "Default")
      (node (ref "IC6") (pin "1") (pinfunction "OUT_1") (pintype "output"))
      (node (ref "R19") (pin "2") (pinfunction "2_2") (pintype "passive"))
      (node (ref "R49") (pin "1") (pinfunction "1_1") (pintype "passive"))
      (node (ref "R6") (pin "1") (pinfunction "1_1") (pintype "passive"))
    )
    (net (code "16") (name "/VCA_OUT") (class "Default")
      (node (ref "C11") (pin "1") (pinfunction "1_1") (pintype "passive"))
      (node (ref "C12") (pin "1") (pinfunction "1_1") (pintype "passive"))
      (node (ref "IC16") (pin "8") (pinfunction "OUT_8") (pintype "output"))
      (node (ref "IC6") (pin "8") (pinfunction "OUT_8") (pintype "output"))
      (node (ref "R24") (pin "1") (pinfunction "1_1") (pintype "passive"))
      (node (ref "R28") (pin "2") (pinfunction "2_2") (pintype "passive"))
      (node (ref "R36") (pin "2") (pinfunction "2_2") (pintype "passive"))
      (node (ref "R52") (pin "2") (pinfunction "2_2") (pintype "passive"))
    )
    (net (code "17") (name "/V_REF") (class "Default")
      (node (ref "IC13") (pin "1") (pinfunction "C_1") (pintype "passive"))
      (node (ref "R13") (pin "2") (pinfunction "2_2") (pintype "passive"))
      (node (ref "R3") (pin "2") (pinfunction "2_2") (pintype "passive"))
      (node (ref "R37") (pin "2") (pinfunction "2_2") (pintype "passive"))
      (node (ref "R61") (pin "2") (pinfunction "2_2") (pintype "passive"))
      (node (ref "R93") (pin "1") (pinfunction "1_1") (pintype "passive"))
    )
    (net (code "18") (name "CLAMP_REF") (class "Default")
      (node (ref "D1") (pin "3") (pinfunction "AA_3") (pintype "passive"))
      (node (ref "D2") (pin "3") (pinfunction "AA_3") (pintype "passive"))
    )
    (net (code "19") (name "GND") (class "Default")
      (node (ref "140K1") (pin "1") (pinfunction "1_1") (pintype "passive"))
      (node (ref "140K2") (pin "1") (pinfunction "1_1") (pintype "passive"))
      (node (ref "3I") (pin "P2") (pinfunction "-2_P2") (pintype "bidirectional"))
      (node (ref "3O") (pin "P2") (pinfunction "-2_P2") (pintype "bidirectional"))
      (node (ref "5I") (pin "P3") (pinfunction "-3_P3") (pintype "bidirectional"))
      (node (ref "5O") (pin "P3") (pinfunction "-3_P3") (pintype "bidirectional"))
      (node (ref "C1") (pin "-") (pinfunction "-_-") (pintype "passive"))
      (node (ref "C10") (pin "2") (pinfunction "2_2") (pintype "passive"))
      (node (ref "C101") (pin "2") (pinfunction "2_2") (pintype "passive"))
      (node (ref "C102") (pin "2") (pinfunction "2_2") (pintype "passive"))
      (node (ref "C2") (pin "+") (pinfunction "+_+") (pintype "passive"))
      (node (ref "C201") (pin "2") (pinfunction "2_2") (pintype "passive"))
      (node (ref "C202") (pin "2") (pinfunction "2_2") (pintype "passive"))
      (node (ref "C27") (pin "2") (pinfunction "2_2") (pintype "passive"))
      (node (ref "C28") (pin "2") (pinfunction "2_2") (pintype "passive"))
      (node (ref "C3") (pin "2") (pinfunction "2_2") (pintype "passive"))
      (node (ref "C5") (pin "2") (pinfunction "2_2") (pintype "passive"))
      (node (ref "C7") (pin "2") (pinfunction "2_2") (pintype "passive"))
      (node (ref "C8") (pin "2") (pinfunction "2_2") (pintype "passive"))
      (node (ref "C9") (pin "2") (pinfunction "2_2") (pintype "passive"))
      (node (ref "IC1") (pin "10") (pinfunction "+IN_10") (pintype "input"))
      (node (ref "IC1") (pin "12") (pinfunction "+IN_12") (pintype "input"))
      (node (ref "IC1") (pin "3") (pinfunction "+IN_3") (pintype "input"))
      (node (ref "IC1") (pin "5") (pinfunction "+IN_5") (pintype "input"))
      (node (ref "IC11") (pin "5") (pinfunction "+IN_5") (pintype "input"))
      (node (ref "IC13") (pin "2") (pinfunction "A_2") (pintype "passive"))
      (node (ref "IC14") (pin "12") (pinfunction "+IN_12") (pintype "input"))
      (node (ref "IC14") (pin "3") (pinfunction "+IN_3") (pintype "input"))
      (node (ref "IC16") (pin "10") (pinfunction "+IN_10") (pintype "input"))
      (node (ref "IC6") (pin "10") (pinfunction "+IN_10") (pintype "input"))
      (node (ref "IC7") (pin "5") (pinfunction "+IN_5") (pintype "input"))
      (node (ref "IN_1") (pin "P$1") (pinfunction "5_P$1") (pintype "passive"))
      (node (ref "IN_2") (pin "P$1") (pinfunction "5_P$1") (pintype "passive"))
      (node (ref "IN_3") (pin "P$1") (pinfunction "5_P$1") (pintype "passive"))
      (node (ref "IN_4") (pin "P$1") (pinfunction "5_P$1") (pintype "passive"))
      (node (ref "OFFSET_LINA") (pin "1") (pinfunction "A_1") (pintype "passive"))
      (node (ref "OFFSET_REF") (pin "1") (pinfunction "A_1") (pintype "passive"))
      (node (ref "OUT_A+") (pin "P$1") (pinfunction "5_P$1") (pintype "passive"))
      (node (ref "OUT_B+") (pin "P$1") (pinfunction "5_P$1") (pintype "passive"))
      (node (ref "POT1A") (pin "1") (pinfunction "1_1") (pintype "bidirectional"))
      (node (ref "POT1A") (pin "P$5") (pinfunction "P$1_P$5") (pintype "bidirectional"))
      (node (ref "POT1A") (pin "P$6") (pinfunction "P$1_P$6") (pintype "bidirectional"))
      (node (ref "POT1B") (pin "1") (pinfunction "1_1") (pintype "bidirectional"))
      (node (ref "POT1B") (pin "P$5") (pinfunction "P$1_P$5") (pintype "bidirectional"))
      (node (ref "POT1B") (pin "P$6") (pinfunction "P$1_P$6") (pintype "bidirectional"))
      (node (ref "POT2A") (pin "1") (pinfunction "1_1") (pintype "bidirectional"))
      (node (ref "POT2A") (pin "P$5") (pinfunction "P$1_P$5") (pintype "bidirectional"))
      (node (ref "POT2A") (pin "P$6") (pinfunction "P$1_P$6") (pintype "bidirectional"))
      (node (ref "POT2B") (pin "1") (pinfunction "1_1") (pintype "bidirectional"))
      (node (ref "POT2B") (pin "P$5") (pinfunction "P$1_P$5") (pintype "bidirectional"))
      (node (ref "POT2B") (pin "P$6") (pinfunction "P$1_P$6") (pintype "bidirectional"))
      (node (ref "POT3A") (pin "1") (pinfunction "1_1") (pintype "bidirectional"))
      (node (ref "POT3A") (pin "P$5") (pinfunction "P$1_P$5") (pintype "bidirectional"))
      (node (ref "POT3A") (pin "P$6") (pinfunction "P$1_P$6") (pintype "bidirectional"))
      (node (ref "POT3B") (pin "1") (pinfunction "1_1") (pintype "bidirectional"))
      (node (ref "POT3B") (pin "P$5") (pinfunction "P$1_P$5") (pintype "bidirectional"))
      (node (ref "POT3B") (pin "P$6") (pinfunction "P$1_P$6") (pintype "bidirectional"))
      (node (ref "POT4A") (pin "1") (pinfunction "1_1") (pintype "bidirectional"))
      (node (ref "POT4A") (pin "P$5") (pinfunction "P$1_P$5") (pintype "bidirectional"))
      (node (ref "POT4A") (pin "P$6") (pinfunction "P$1_P$6") (pintype "bidirectional"))
      (node (ref "POT4B") (pin "1") (pinfunction "1_1") (pintype "bidirectional"))
      (node (ref "POT4B") (pin "P$5") (pinfunction "P$1_P$5") (pintype "bidirectional"))
      (node (ref "POT4B") (pin "P$6") (pinfunction "P$1_P$6") (pintype "bidirectional"))
      (node (ref "Q1") (pin "1") (pinfunction "G_1") (pintype "passive"))
      (node (ref "Q2") (pin "1") (pinfunction "G_1") (pintype "passive"))
      (node (ref "R14") (pin "2") (pinfunction "2_2") (pintype "passive"))
      (node (ref "R21") (pin "2") (pinfunction "2_2") (pintype "passive"))
      (node (ref "R27") (pin "2") (pinfunction "2_2") (pintype "passive"))
      (node (ref "R31") (pin "1") (pinfunction "1_1") (pintype "passive"))
      (node (ref "R505") (pin "2") (pinfunction "2_2") (pintype "passive"))
      (node (ref "R506") (pin "2") (pinfunction "2_2") (pintype "passive"))
      (node (ref "R507") (pin "2") (pinfunction "2_2") (pintype "passive"))
      (node (ref "R508") (pin "2") (pinfunction "2_2") (pintype "passive"))
      (node (ref "SJ1") (pin "1") (pinfunction "1_1") (pintype "passive"))
      (node (ref "SJ2") (pin "1") (pinfunction "1_1") (pintype "passive"))
      (node (ref "SJ3") (pin "1") (pinfunction "1_1") (pintype "passive"))
      (node (ref "SJ4") (pin "1") (pinfunction "1_1") (pintype "passive"))
      (node (ref "SJ5") (pin "1") (pinfunction "1_1") (pintype "passive"))
      (node (ref "SJ6") (pin "1") (pinfunction "1_1") (pintype "passive"))
      (node (ref "SJ7") (pin "1") (pinfunction "1_1") (pintype "passive"))
      (node (ref "SJ8") (pin "1") (pinfunction "1_1") (pintype "passive"))
      (node (ref "SV1") (pin "3") (pinfunction "3_3") (pintype "passive"))
      (node (ref "SV1") (pin "4") (pinfunction "4_4") (pintype "passive"))
      (node (ref "SV1") (pin "5") (pinfunction "5_5") (pintype "passive"))
      (node (ref "SV1") (pin "6") (pinfunction "6_6") (pintype "passive"))
      (node (ref "SV1") (pin "7") (pinfunction "7_7") (pintype "passive"))
      (node (ref "SV1") (pin "8") (pinfunction "8_8") (pintype "passive"))
    )
    (net (code "20") (name "Net-(3I--1)") (class "Default")
      (node (ref "3I") (pin "P1") (pinfunction "-1_P1") (pintype "bidirectional"))
      (node (ref "R205") (pin "2") (pinfunction "2_2") (pintype "passive"))
    )
    (net (code "21") (name "Net-(3I--3)") (class "Default")
      (node (ref "3I") (pin "P3") (pinfunction "-3_P3") (pintype "bidirectional"))
      (node (ref "R105") (pin "2") (pinfunction "2_2") (pintype "passive"))
    )
    (net (code "22") (name "Net-(3O--1)") (class "Default")
      (node (ref "3O") (pin "P1") (pinfunction "-1_P1") (pintype "bidirectional"))
      (node (ref "OUT_A+") (pin "P$2") (pinfunction "4_P$2") (pintype "passive"))
    )
    (net (code "23") (name "Net-(3O--3)") (class "Default")
      (node (ref "3O") (pin "P3") (pinfunction "-3_P3") (pintype "bidirectional"))
      (node (ref "OUT_B+") (pin "P$2") (pinfunction "4_P$2") (pintype "passive"))
    )
    (net (code "24") (name "Net-(5I--1)") (class "Default")
      (node (ref "5I") (pin "P1") (pinfunction "-1_P1") (pintype "bidirectional"))
      (node (ref "IN_4") (pin "P$2") (pinfunction "4_P$2") (pintype "passive"))
    )
    (net (code "25") (name "Net-(5I--2)") (class "Default")
      (node (ref "5I") (pin "P2") (pinfunction "-2_P2") (pintype "bidirectional"))
      (node (ref "IN_3") (pin "P$2") (pinfunction "4_P$2") (pintype "passive"))
    )
    (net (code "26") (name "Net-(5I--4)") (class "Default")
      (node (ref "5I") (pin "P4") (pinfunction "-4_P4") (pintype "bidirectional"))
      (node (ref "IN_2") (pin "P$2") (pinfunction "4_P$2") (pintype "passive"))
    )
    (net (code "27") (name "Net-(5I--5)") (class "Default")
      (node (ref "5I") (pin "P5") (pinfunction "-5_P5") (pintype "bidirectional"))
      (node (ref "IN_1") (pin "P$2") (pinfunction "4_P$2") (pintype "passive"))
    )
    (net (code "28") (name "Net-(5O--1)") (class "Default")
      (node (ref "5O") (pin "P1") (pinfunction "-1_P1") (pintype "bidirectional"))
      (node (ref "IC2") (pin "12") (pinfunction "+IN_12") (pintype "input"))
      (node (ref "IN_1") (pin "P$3") (pinfunction "3_P$3") (pintype "passive"))
      (node (ref "R505") (pin "1") (pinfunction "1_1") (pintype "passive"))
    )
    (net (code "29") (name "Net-(5O--2)") (class "Default")
      (node (ref "5O") (pin "P2") (pinfunction "-2_P2") (pintype "bidirectional"))
      (node (ref "IC2") (pin "10") (pinfunction "+IN_10") (pintype "input"))
      (node (ref "IN_2") (pin "P$3") (pinfunction "3_P$3") (pintype "passive"))
      (node (ref "R506") (pin "1") (pinfunction "1_1") (pintype "passive"))
    )
    (net (code "30") (name "Net-(5O--4)") (class "Default")
      (node (ref "5O") (pin "P4") (pinfunction "-4_P4") (pintype "bidirectional"))
      (node (ref "IC2") (pin "5") (pinfunction "+IN_5") (pintype "input"))
      (node (ref "IN_3") (pin "P$3") (pinfunction "3_P$3") (pintype "passive"))
      (node (ref "R507") (pin "1") (pinfunction "1_1") (pintype "passive"))
    )
    (net (code "31") (name "Net-(5O--5)") (class "Default")
      (node (ref "5O") (pin "P5") (pinfunction "-5_P5") (pintype "bidirectional"))
      (node (ref "IC2") (pin "3") (pinfunction "+IN_3") (pintype "input"))
      (node (ref "IN_4") (pin "P$3") (pinfunction "3_P$3") (pintype "passive"))
      (node (ref "R508") (pin "1") (pinfunction "1_1") (pintype "passive"))
    )
    (net (code "32") (name "Net-(140K1-Pad2)") (class "Default")
      (node (ref "140K1") (pin "2") (pinfunction "2_2") (pintype "passive"))
      (node (ref "R59") (pin "1") (pinfunction "1_1") (pintype "passive"))
      (node (ref "R61") (pin "1") (pinfunction "1_1") (pintype "passive"))
    )
    (net (code "33") (name "Net-(140K2-Pad2)") (class "Default")
      (node (ref "140K2") (pin "2") (pinfunction "2_2") (pintype "passive"))
      (node (ref "R34") (pin "1") (pinfunction "1_1") (pintype "passive"))
      (node (ref "R37") (pin "1") (pinfunction "1_1") (pintype "passive"))
    )
    (net (code "34") (name "Net-(C5-Pad1)") (class "Default")
      (node (ref "C5") (pin "1") (pinfunction "1_1") (pintype "passive"))
      (node (ref "R12") (pin "1") (pinfunction "1_1") (pintype "passive"))
    )
    (net (code "35") (name "Net-(C7-Pad1)") (class "Default")
      (node (ref "C7") (pin "1") (pinfunction "1_1") (pintype "passive"))
      (node (ref "R60") (pin "1") (pinfunction "1_1") (pintype "passive"))
    )
    (net (code "36") (name "Net-(C8-Pad1)") (class "Default")
      (node (ref "C8") (pin "1") (pinfunction "1_1") (pintype "passive"))
      (node (ref "R35") (pin "1") (pinfunction "1_1") (pintype "passive"))
    )
    (net (code "37") (name "Net-(C10-Pad1)") (class "Default")
      (node (ref "C10") (pin "1") (pinfunction "1_1") (pintype "passive"))
      (node (ref "R50") (pin "1") (pinfunction "1_1") (pintype "passive"))
    )
    (net (code "38") (name "Net-(D1-K2)") (class "Default")
      (node (ref "D1") (pin "2") (pinfunction "K2_2") (pintype "passive"))
      (node (ref "IC5") (pin "11") (pinfunction "CTRL_11") (pintype "input"))
      (node (ref "R51") (pin "1") (pinfunction "1_1") (pintype "passive"))
    )
    (net (code "39") (name "Net-(D2-K2)") (class "Default")
      (node (ref "D2") (pin "2") (pinfunction "K2_2") (pintype "passive"))
      (node (ref "IC15") (pin "11") (pinfunction "CTRL_11") (pintype "input"))
      (node (ref "R53") (pin "1") (pinfunction "1_1") (pintype "passive"))
    )
    (net (code "40") (name "Net-(IC1A--IN)") (class "Default")
      (node (ref "IC1") (pin "2") (pinfunction "-IN_2") (pintype "input"))
      (node (ref "R101") (pin "1") (pinfunction "1_1") (pintype "passive"))
      (node (ref "R102") (pin "1") (pinfunction "1_1") (pintype "passive"))
      (node (ref "R103") (pin "1") (pinfunction "1_1") (pintype "passive"))
      (node (ref "R104") (pin "1") (pinfunction "1_1") (pintype "passive"))
      (node (ref "R105") (pin "1") (pinfunction "1_1") (pintype "passive"))
      (node (ref "R106") (pin "1") (pinfunction "1_1") (pintype "passive"))
    )
    (net (code "41") (name "Net-(IC1A-OUT)") (class "Default")
      (node (ref "IC1") (pin "1") (pinfunction "OUT_1") (pintype "output"))
      (node (ref "R106") (pin "2") (pinfunction "2_2") (pintype "passive"))
      (node (ref "R107") (pin "1") (pinfunction "1_1") (pintype "passive"))
    )
    (net (code "42") (name "Net-(IC1B--IN)") (class "Default")
      (node (ref "IC1") (pin "6") (pinfunction "-IN_6") (pintype "input"))
      (node (ref "R107") (pin "2") (pinfunction "2_2") (pintype "passive"))
      (node (ref "R108") (pin "1") (pinfunction "1_1") (pintype "passive"))
    )
    (net (code "43") (name "Net-(IC1B-OUT)") (class "Default")
      (node (ref "IC1") (pin "7") (pinfunction "OUT_7") (pintype "output"))
      (node (ref "R108") (pin "2") (pinfunction "2_2") (pintype "passive"))
      (node (ref "R110") (pin "1") (pinfunction "1_1") (pintype "passive"))
    )
    (net (code "44") (name "Net-(IC1C--IN)") (class "Default")
      (node (ref "IC1") (pin "9") (pinfunction "-IN_9") (pintype "input"))
      (node (ref "R207") (pin "2") (pinfunction "2_2") (pintype "passive"))
      (node (ref "R208") (pin "1") (pinfunction "1_1") (pintype "passive"))
    )
    (net (code "45") (name "Net-(IC1C-OUT)") (class "Default")
      (node (ref "IC1") (pin "8") (pinfunction "OUT_8") (pintype "output"))
      (node (ref "R208") (pin "2") (pinfunction "2_2") (pintype "passive"))
      (node (ref "R210") (pin "1") (pinfunction "1_1") (pintype "passive"))
    )
    (net (code "46") (name "Net-(IC1D--IN)") (class "Default")
      (node (ref "IC1") (pin "13") (pinfunction "-IN_13") (pintype "input"))
      (node (ref "R201") (pin "1") (pinfunction "1_1") (pintype "passive"))
      (node (ref "R202") (pin "1") (pinfunction "1_1") (pintype "passive"))
      (node (ref "R203") (pin "1") (pinfunction "1_1") (pintype "passive"))
      (node (ref "R204") (pin "1") (pinfunction "1_1") (pintype "passive"))
      (node (ref "R205") (pin "1") (pinfunction "1_1") (pintype "passive"))
      (node (ref "R206") (pin "1") (pinfunction "1_1") (pintype "passive"))
    )
    (net (code "47") (name "Net-(IC1D-OUT)") (class "Default")
      (node (ref "IC1") (pin "14") (pinfunction "OUT_14") (pintype "output"))
      (node (ref "R206") (pin "2") (pinfunction "2_2") (pintype "passive"))
      (node (ref "R207") (pin "1") (pinfunction "1_1") (pintype "passive"))
    )
    (net (code "48") (name "Net-(IC3D-IN)") (class "Default")
      (node (ref "IC3") (pin "15") (pinfunction "IN_15") (pintype "input"))
      (node (ref "R59") (pin "2") (pinfunction "2_2") (pintype "passive"))
      (node (ref "R60") (pin "2") (pinfunction "2_2") (pintype "passive"))
    )
    (net (code "49") (name "Net-(IC3D-OUT)") (class "Default")
      (node (ref "C6") (pin "2") (pinfunction "2_2") (pintype "passive"))
      (node (ref "IC3") (pin "13") (pinfunction "OUT_13") (pintype "output"))
      (node (ref "IC7") (pin "13") (pinfunction "-IN_13") (pintype "input"))
      (node (ref "R58") (pin "1") (pinfunction "1_1") (pintype "passive"))
    )
    (net (code "50") (name "Net-(IC4B-+IN)") (class "Default")
      (node (ref "C3") (pin "1") (pinfunction "1_1") (pintype "passive"))
      (node (ref "IC4") (pin "5") (pinfunction "+IN_5") (pintype "input"))
      (node (ref "OFFSET_LINA") (pin "2") (pinfunction "S_2") (pintype "passive"))
    )
    (net (code "51") (name "Net-(IC5C-IN)") (class "Default")
      (node (ref "IC5") (pin "10") (pinfunction "IN_10") (pintype "input"))
      (node (ref "R12") (pin "2") (pinfunction "2_2") (pintype "passive"))
      (node (ref "R6") (pin "2") (pinfunction "2_2") (pintype "passive"))
    )
    (net (code "52") (name "Net-(IC5C-OUT)") (class "Default")
      (node (ref "C12") (pin "2") (pinfunction "2_2") (pintype "passive"))
      (node (ref "IC5") (pin "12") (pinfunction "OUT_12") (pintype "output"))
      (node (ref "IC6") (pin "9") (pinfunction "-IN_9") (pintype "input"))
      (node (ref "R36") (pin "1") (pinfunction "1_1") (pintype "passive"))
    )
    (net (code "53") (name "Net-(IC6A-+IN)") (class "Default")
      (node (ref "IC6") (pin "3") (pinfunction "+IN_3") (pintype "input"))
      (node (ref "R14") (pin "1") (pinfunction "1_1") (pintype "passive"))
      (node (ref "R16") (pin "2") (pinfunction "2_2") (pintype "passive"))
    )
    (net (code "54") (name "Net-(IC6A--IN)") (class "Default")
      (node (ref "IC6") (pin "2") (pinfunction "-IN_2") (pintype "input"))
      (node (ref "R19") (pin "1") (pinfunction "1_1") (pintype "passive"))
      (node (ref "R20") (pin "2") (pinfunction "2_2") (pintype "passive"))
    )
    (net (code "55") (name "Net-(IC7B--IN)") (class "Default")
      (node (ref "IC7") (pin "6") (pinfunction "-IN_6") (pintype "input"))
      (node (ref "R18") (pin "1") (pinfunction "1_1") (pintype "passive"))
      (node (ref "R55") (pin "2") (pinfunction "2_2") (pintype "passive"))
    )
    (net (code "56") (name "Net-(IC7B-OUT)") (class "Default")
      (node (ref "IC7") (pin "7") (pinfunction "OUT_7") (pintype "output"))
      (node (ref "R18") (pin "2") (pinfunction "2_2") (pintype "passive"))
      (node (ref "R58") (pin "2") (pinfunction "2_2") (pintype "passive"))
    )
    (net (code "57") (name "Net-(IC8A-+IN)") (class "Default")
      (node (ref "IC8") (pin "3") (pinfunction "+IN_3") (pintype "input"))
      (node (ref "R21") (pin "1") (pinfunction "1_1") (pintype "passive"))
      (node (ref "R22") (pin "2") (pinfunction "2_2") (pintype "passive"))
    )
    (net (code "58") (name "Net-(IC8A--IN)") (class "Default")
      (node (ref "IC8") (pin "2") (pinfunction "-IN_2") (pintype "input"))
      (node (ref "R23") (pin "1") (pinfunction "1_1") (pintype "passive"))
      (node (ref "R24") (pin "2") (pinfunction "2_2") (pintype "passive"))
    )
    (net (code "59") (name "Net-(IC9A-+IN)") (class "Default")
      (node (ref "IC9") (pin "3") (pinfunction "+IN_3") (pintype "input"))
      (node (ref "R28") (pin "1") (pinfunction "1_1") (pintype "passive"))
      (node (ref "R29") (pin "2") (pinfunction "2_2") (pintype "passive"))
    )
    (net (code "60") (name "Net-(IC9A--IN)") (class "Default")
      (node (ref "IC9") (pin "2") (pinfunction "-IN_2") (pintype "input"))
      (node (ref "R30") (pin "1") (pinfunction "1_1") (pintype "passive"))
      (node (ref "R31") (pin "2") (pinfunction "2_2") (pintype "passive"))
    )
    (net (code "61") (name "Net-(IC10D-IN)") (class "Default")
      (node (ref "IC10") (pin "15") (pinfunction "IN_15") (pintype "input"))
      (node (ref "R34") (pin "2") (pinfunction "2_2") (pintype "passive"))
      (node (ref "R35") (pin "2") (pinfunction "2_2") (pintype "passive"))
    )
    (net (code "62") (name "Net-(IC10D-OUT)") (class "Default")
      (node (ref "C4") (pin "2") (pinfunction "2_2") (pintype "passive"))
      (node (ref "IC10") (pin "13") (pinfunction "OUT_13") (pintype "output"))
      (node (ref "IC11") (pin "13") (pinfunction "-IN_13") (pintype "input"))
      (node (ref "R33") (pin "1") (pinfunction "1_1") (pintype "passive"))
    )
    (net (code "63") (name "Net-(IC11B--IN)") (class "Default")
      (node (ref "IC11") (pin "6") (pinfunction "-IN_6") (pintype "input"))
      (node (ref "R32") (pin "2") (pinfunction "2_2") (pintype "passive"))
      (node (ref "R40") (pin "1") (pinfunction "1_1") (pintype "passive"))
    )
    (net (code "64") (name "Net-(IC11B-OUT)") (class "Default")
      (node (ref "IC11") (pin "7") (pinfunction "OUT_7") (pintype "output"))
      (node (ref "R33") (pin "2") (pinfunction "2_2") (pintype "passive"))
      (node (ref "R40") (pin "2") (pinfunction "2_2") (pintype "passive"))
    )
    (net (code "65") (name "Net-(IC14A--IN)") (class "Default")
      (node (ref "IC14") (pin "2") (pinfunction "-IN_2") (pintype "input"))
      (node (ref "R39") (pin "2") (pinfunction "2_2") (pintype "passive"))
      (node (ref "R42") (pin "1") (pinfunction "1_1") (pintype "passive"))
    )
    (net (code "66") (name "Net-(IC14A-OUT)") (class "Default")
      (node (ref "IC14") (pin "1") (pinfunction "OUT_1") (pintype "output"))
      (node (ref "R15") (pin "2") (pinfunction "2_2") (pintype "passive"))
      (node (ref "R39") (pin "1") (pinfunction "1_1") (pintype "passive"))
    )
    (net (code "67") (name "Net-(IC14B-+IN)") (class "Default")
      (node (ref "IC14") (pin "5") (pinfunction "+IN_5") (pintype "input"))
      (node (ref "R26") (pin "1") (pinfunction "1_1") (pintype "passive"))
      (node (ref "R27") (pin "1") (pinfunction "1_1") (pintype "passive"))
    )
    (net (code "68") (name "Net-(IC14B--IN)") (class "Default")
      (node (ref "IC14") (pin "6") (pinfunction "-IN_6") (pintype "input"))
      (node (ref "R15") (pin "1") (pinfunction "1_1") (pintype "passive"))
      (node (ref "R38") (pin "2") (pinfunction "2_2") (pintype "passive"))
      (node (ref "R5") (pin "1") (pinfunction "1_1") (pintype "passive"))
    )
    (net (code "69") (name "Net-(IC14D--IN)") (class "Default")
      (node (ref "IC14") (pin "13") (pinfunction "-IN_13") (pintype "input"))
      (node (ref "R17") (pin "1") (pinfunction "1_1") (pintype "passive"))
      (node (ref "R25") (pin "2") (pinfunction "2_2") (pintype "passive"))
    )
    (net (code "70") (name "Net-(IC15C-IN)") (class "Default")
      (node (ref "IC15") (pin "10") (pinfunction "IN_10") (pintype "input"))
      (node (ref "R49") (pin "2") (pinfunction "2_2") (pintype "passive"))
      (node (ref "R50") (pin "2") (pinfunction "2_2") (pintype "passive"))
    )
    (net (code "71") (name "Net-(IC15C-OUT)") (class "Default")
      (node (ref "C11") (pin "2") (pinfunction "2_2") (pintype "passive"))
      (node (ref "IC15") (pin "12") (pinfunction "OUT_12") (pintype "output"))
      (node (ref "IC16") (pin "9") (pinfunction "-IN_9") (pintype "input"))
      (node (ref "R52") (pin "1") (pinfunction "1_1") (pintype "passive"))
    )
    (net (code "72") (name "Net-(OFFSET_LINA-E)") (class "Default")
      (node (ref "OFFSET_LINA") (pin "3") (pinfunction "E_3") (pintype "passive"))
      (node (ref "R13") (pin "1") (pinfunction "1_1") (pintype "passive"))
    )
    (net (code "73") (name "Net-(OFFSET_REF-E)") (class "Default")
      (node (ref "OFFSET_REF") (pin "3") (pinfunction "E_3") (pintype "passive"))
      (node (ref "R3") (pin "1") (pinfunction "1_1") (pintype "passive"))
    )
    (net (code "74") (name "Net-(OFFSET_REF-S)") (class "Default")
      (node (ref "C9") (pin "1") (pinfunction "1_1") (pintype "passive"))
      (node (ref "OFFSET_REF") (pin "2") (pinfunction "S_2") (pintype "passive"))
      (node (ref "R17") (pin "2") (pinfunction "2_2") (pintype "passive"))
    )
    (net (code "75") (name "Net-(OUT_A+-3)") (class "Default")
      (node (ref "OUT_A+") (pin "P$3") (pinfunction "3_P$3") (pintype "passive"))
      (node (ref "R110") (pin "2") (pinfunction "2_2") (pintype "passive"))
    )
    (net (code "76") (name "Net-(OUT_B+-3)") (class "Default")
      (node (ref "OUT_B+") (pin "P$3") (pinfunction "3_P$3") (pintype "passive"))
      (node (ref "R210") (pin "2") (pinfunction "2_2") (pintype "passive"))
    )
    (net (code "77") (name "Net-(POT1A-Pad2)") (class "Default")
      (node (ref "POT1A") (pin "2") (pinfunction "2_2") (pintype "bidirectional"))
      (node (ref "R1") (pin "1") (pinfunction "1_1") (pintype "passive"))
      (node (ref "R101") (pin "2") (pinfunction "2_2") (pintype "passive"))
    )
    (net (code "78") (name "Net-(POT1A-Pad3)") (class "Default")
      (node (ref "POT1A") (pin "3") (pinfunction "3_3") (pintype "bidirectional"))
      (node (ref "POT1B") (pin "3") (pinfunction "3_3") (pintype "bidirectional"))
    )
    (net (code "79") (name "Net-(POT1B-Pad2)") (class "Default")
      (node (ref "POT1B") (pin "2") (pinfunction "2_2") (pintype "bidirectional"))
      (node (ref "R11") (pin "1") (pinfunction "1_1") (pintype "passive"))
      (node (ref "R201") (pin "2") (pinfunction "2_2") (pintype "passive"))
    )
    (net (code "80") (name "Net-(POT2A-Pad2)") (class "Default")
      (node (ref "POT2A") (pin "2") (pinfunction "2_2") (pintype "bidirectional"))
      (node (ref "R102") (pin "2") (pinfunction "2_2") (pintype "passive"))
      (node (ref "R2") (pin "1") (pinfunction "1_1") (pintype "passive"))
    )
    (net (code "81") (name "Net-(POT2A-Pad3)") (class "Default")
      (node (ref "POT2A") (pin "3") (pinfunction "3_3") (pintype "bidirectional"))
      (node (ref "POT2B") (pin "3") (pinfunction "3_3") (pintype "bidirectional"))
    )
    (net (code "82") (name "Net-(POT2B-Pad2)") (class "Default")
      (node (ref "POT2B") (pin "2") (pinfunction "2_2") (pintype "bidirectional"))
      (node (ref "R202") (pin "2") (pinfunction "2_2") (pintype "passive"))
      (node (ref "R8") (pin "1") (pinfunction "1_1") (pintype "passive"))
    )
    (net (code "83") (name "Net-(POT3A-Pad2)") (class "Default")
      (node (ref "POT3A") (pin "2") (pinfunction "2_2") (pintype "bidirectional"))
      (node (ref "R103") (pin "2") (pinfunction "2_2") (pintype "passive"))
      (node (ref "R4") (pin "1") (pinfunction "1_1") (pintype "passive"))
    )
    (net (code "84") (name "Net-(POT3A-Pad3)") (class "Default")
      (node (ref "POT3A") (pin "3") (pinfunction "3_3") (pintype "bidirectional"))
      (node (ref "POT3B") (pin "3") (pinfunction "3_3") (pintype "bidirectional"))
    )
    (net (code "85") (name "Net-(POT3B-Pad2)") (class "Default")
      (node (ref "POT3B") (pin "2") (pinfunction "2_2") (pintype "bidirectional"))
      (node (ref "R203") (pin "2") (pinfunction "2_2") (pintype "passive"))
      (node (ref "R9") (pin "1") (pinfunction "1_1") (pintype "passive"))
    )
    (net (code "86") (name "Net-(POT4A-Pad2)") (class "Default")
      (node (ref "POT4A") (pin "2") (pinfunction "2_2") (pintype "bidirectional"))
      (node (ref "R104") (pin "2") (pinfunction "2_2") (pintype "passive"))
      (node (ref "R7") (pin "1") (pinfunction "1_1") (pintype "passive"))
    )
    (net (code "87") (name "Net-(POT4A-Pad3)") (class "Default")
      (node (ref "POT4A") (pin "3") (pinfunction "3_3") (pintype "bidirectional"))
      (node (ref "POT4B") (pin "3") (pinfunction "3_3") (pintype "bidirectional"))
    )
    (net (code "88") (name "Net-(POT4B-Pad2)") (class "Default")
      (node (ref "POT4B") (pin "2") (pinfunction "2_2") (pintype "bidirectional"))
      (node (ref "R10") (pin "1") (pinfunction "1_1") (pintype "passive"))
      (node (ref "R204") (pin "2") (pinfunction "2_2") (pintype "passive"))
    )
    (net (code "89") (name "Net-(Q1-D)") (class "Default")
      (node (ref "Q1") (pin "3") (pinfunction "D_3") (pintype "passive"))
      (node (ref "SV1") (pin "10") (pinfunction "10_10") (pintype "passive"))
      (node (ref "SV1") (pin "9") (pinfunction "9_9") (pintype "passive"))
    )
    (net (code "90") (name "Net-(Q2-D)") (class "Default")
      (node (ref "Q2") (pin "3") (pinfunction "D_3") (pintype "passive"))
      (node (ref "SV1") (pin "1") (pinfunction "1_1") (pintype "passive"))
      (node (ref "SV1") (pin "2") (pinfunction "2_2") (pintype "passive"))
    )
    (net (code "91") (name "Net-(R1-Pad2)") (class "Default")
      (node (ref "R1") (pin "2") (pinfunction "2_2") (pintype "passive"))
      (node (ref "SJ1") (pin "2") (pinfunction "2_2") (pintype "passive"))
    )
    (net (code "92") (name "Net-(R2-Pad2)") (class "Default")
      (node (ref "R2") (pin "2") (pinfunction "2_2") (pintype "passive"))
      (node (ref "SJ2") (pin "2") (pinfunction "2_2") (pintype "passive"))
    )
    (net (code "93") (name "Net-(R4-Pad2)") (class "Default")
      (node (ref "R4") (pin "2") (pinfunction "2_2") (pintype "passive"))
      (node (ref "SJ3") (pin "2") (pinfunction "2_2") (pintype "passive"))
    )
    (net (code "94") (name "Net-(R7-Pad2)") (class "Default")
      (node (ref "R7") (pin "2") (pinfunction "2_2") (pintype "passive"))
      (node (ref "SJ4") (pin "2") (pinfunction "2_2") (pintype "passive"))
    )
    (net (code "95") (name "Net-(R8-Pad2)") (class "Default")
      (node (ref "R8") (pin "2") (pinfunction "2_2") (pintype "passive"))
      (node (ref "SJ6") (pin "2") (pinfunction "2_2") (pintype "passive"))
    )
    (net (code "96") (name "Net-(R9-Pad2)") (class "Default")
      (node (ref "R9") (pin "2") (pinfunction "2_2") (pintype "passive"))
      (node (ref "SJ7") (pin "2") (pinfunction "2_2") (pintype "passive"))
    )
    (net (code "97") (name "Net-(R10-Pad2)") (class "Default")
      (node (ref "R10") (pin "2") (pinfunction "2_2") (pintype "passive"))
      (node (ref "SJ8") (pin "2") (pinfunction "2_2") (pintype "passive"))
    )
    (net (code "98") (name "Net-(R11-Pad2)") (class "Default")
      (node (ref "R11") (pin "2") (pinfunction "2_2") (pintype "passive"))
      (node (ref "SJ5") (pin "2") (pinfunction "2_2") (pintype "passive"))
    )
    (net (code "99") (name "unconnected-(D1-K1-Pad1)") (class "Default")
      (node (ref "D1") (pin "1") (pinfunction "K1_1") (pintype "passive"))
    )
    (net (code "100") (name "unconnected-(D2-K1-Pad1)") (class "Default")
      (node (ref "D2") (pin "1") (pinfunction "K1_1") (pintype "passive"))
    )
    (net (code "101") (name "unconnected-(R29-Pad1)") (class "Default")
      (node (ref "R29") (pin "1") (pinfunction "1_1") (pintype "passive"))
    )
  )
)
